# TeensySensorV6_1.net
KiCad netlist of a schematic drawn in EasyEDA Pro
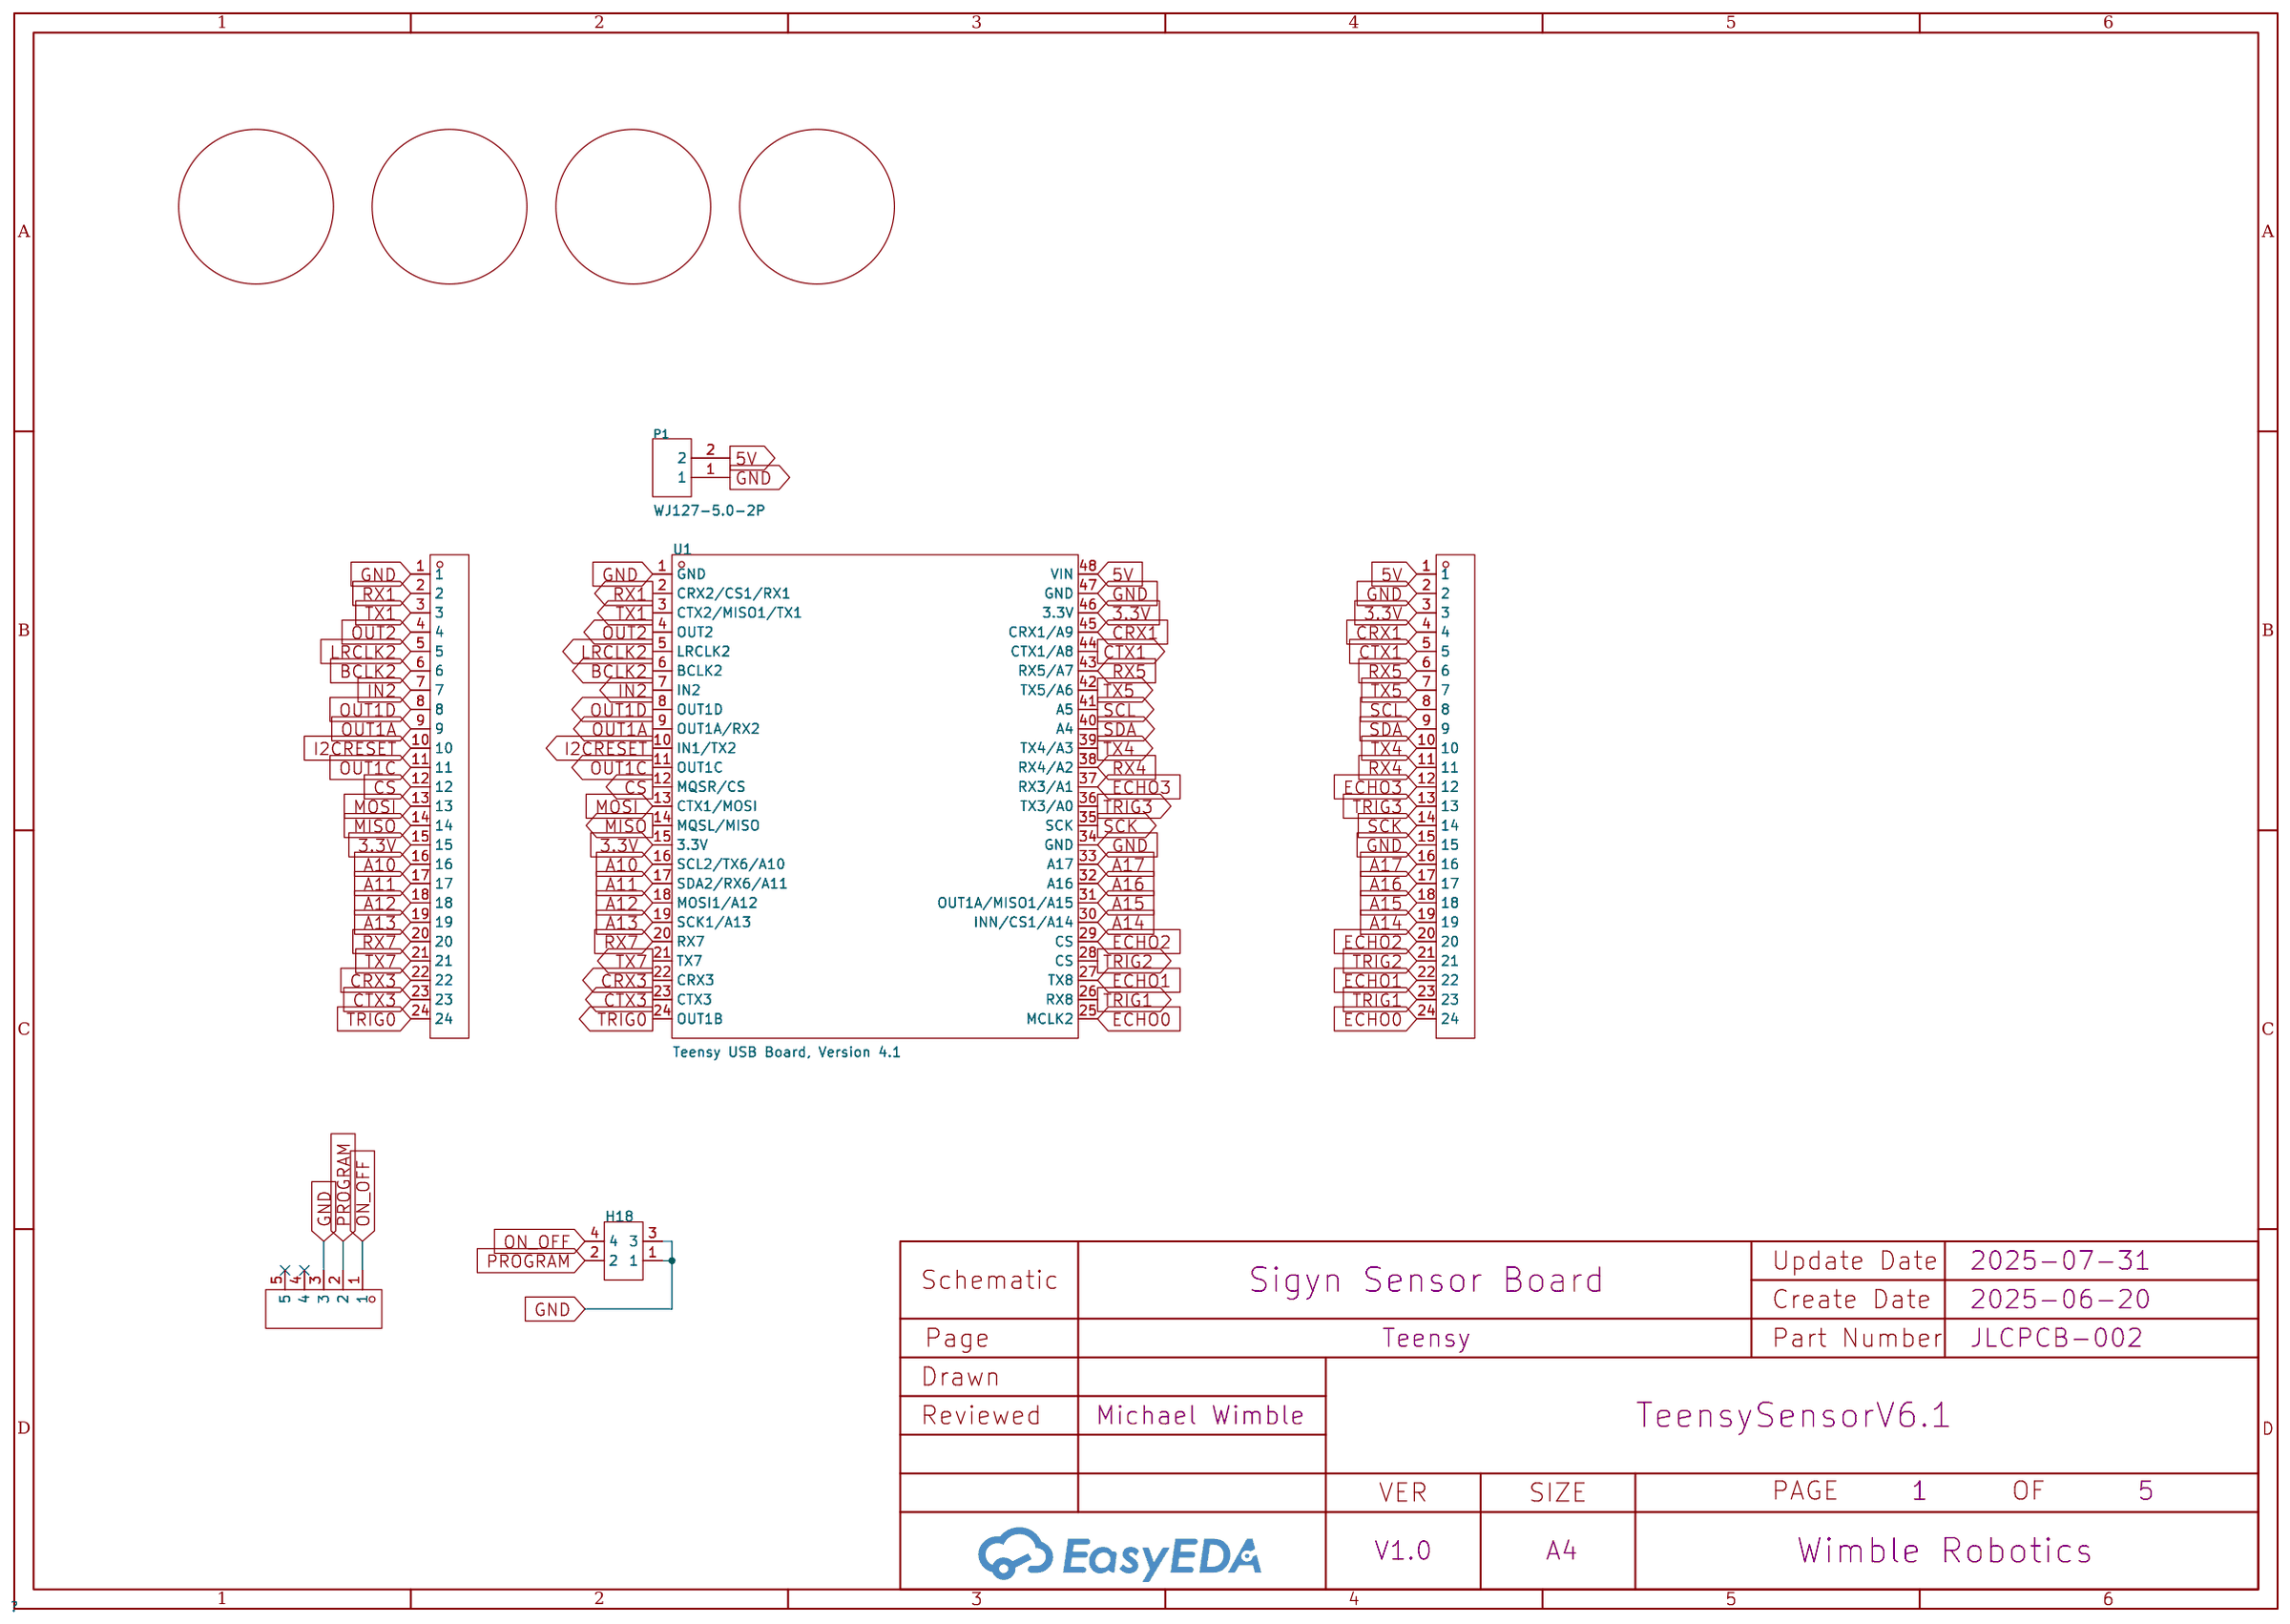
[diagram p0: Teensy]
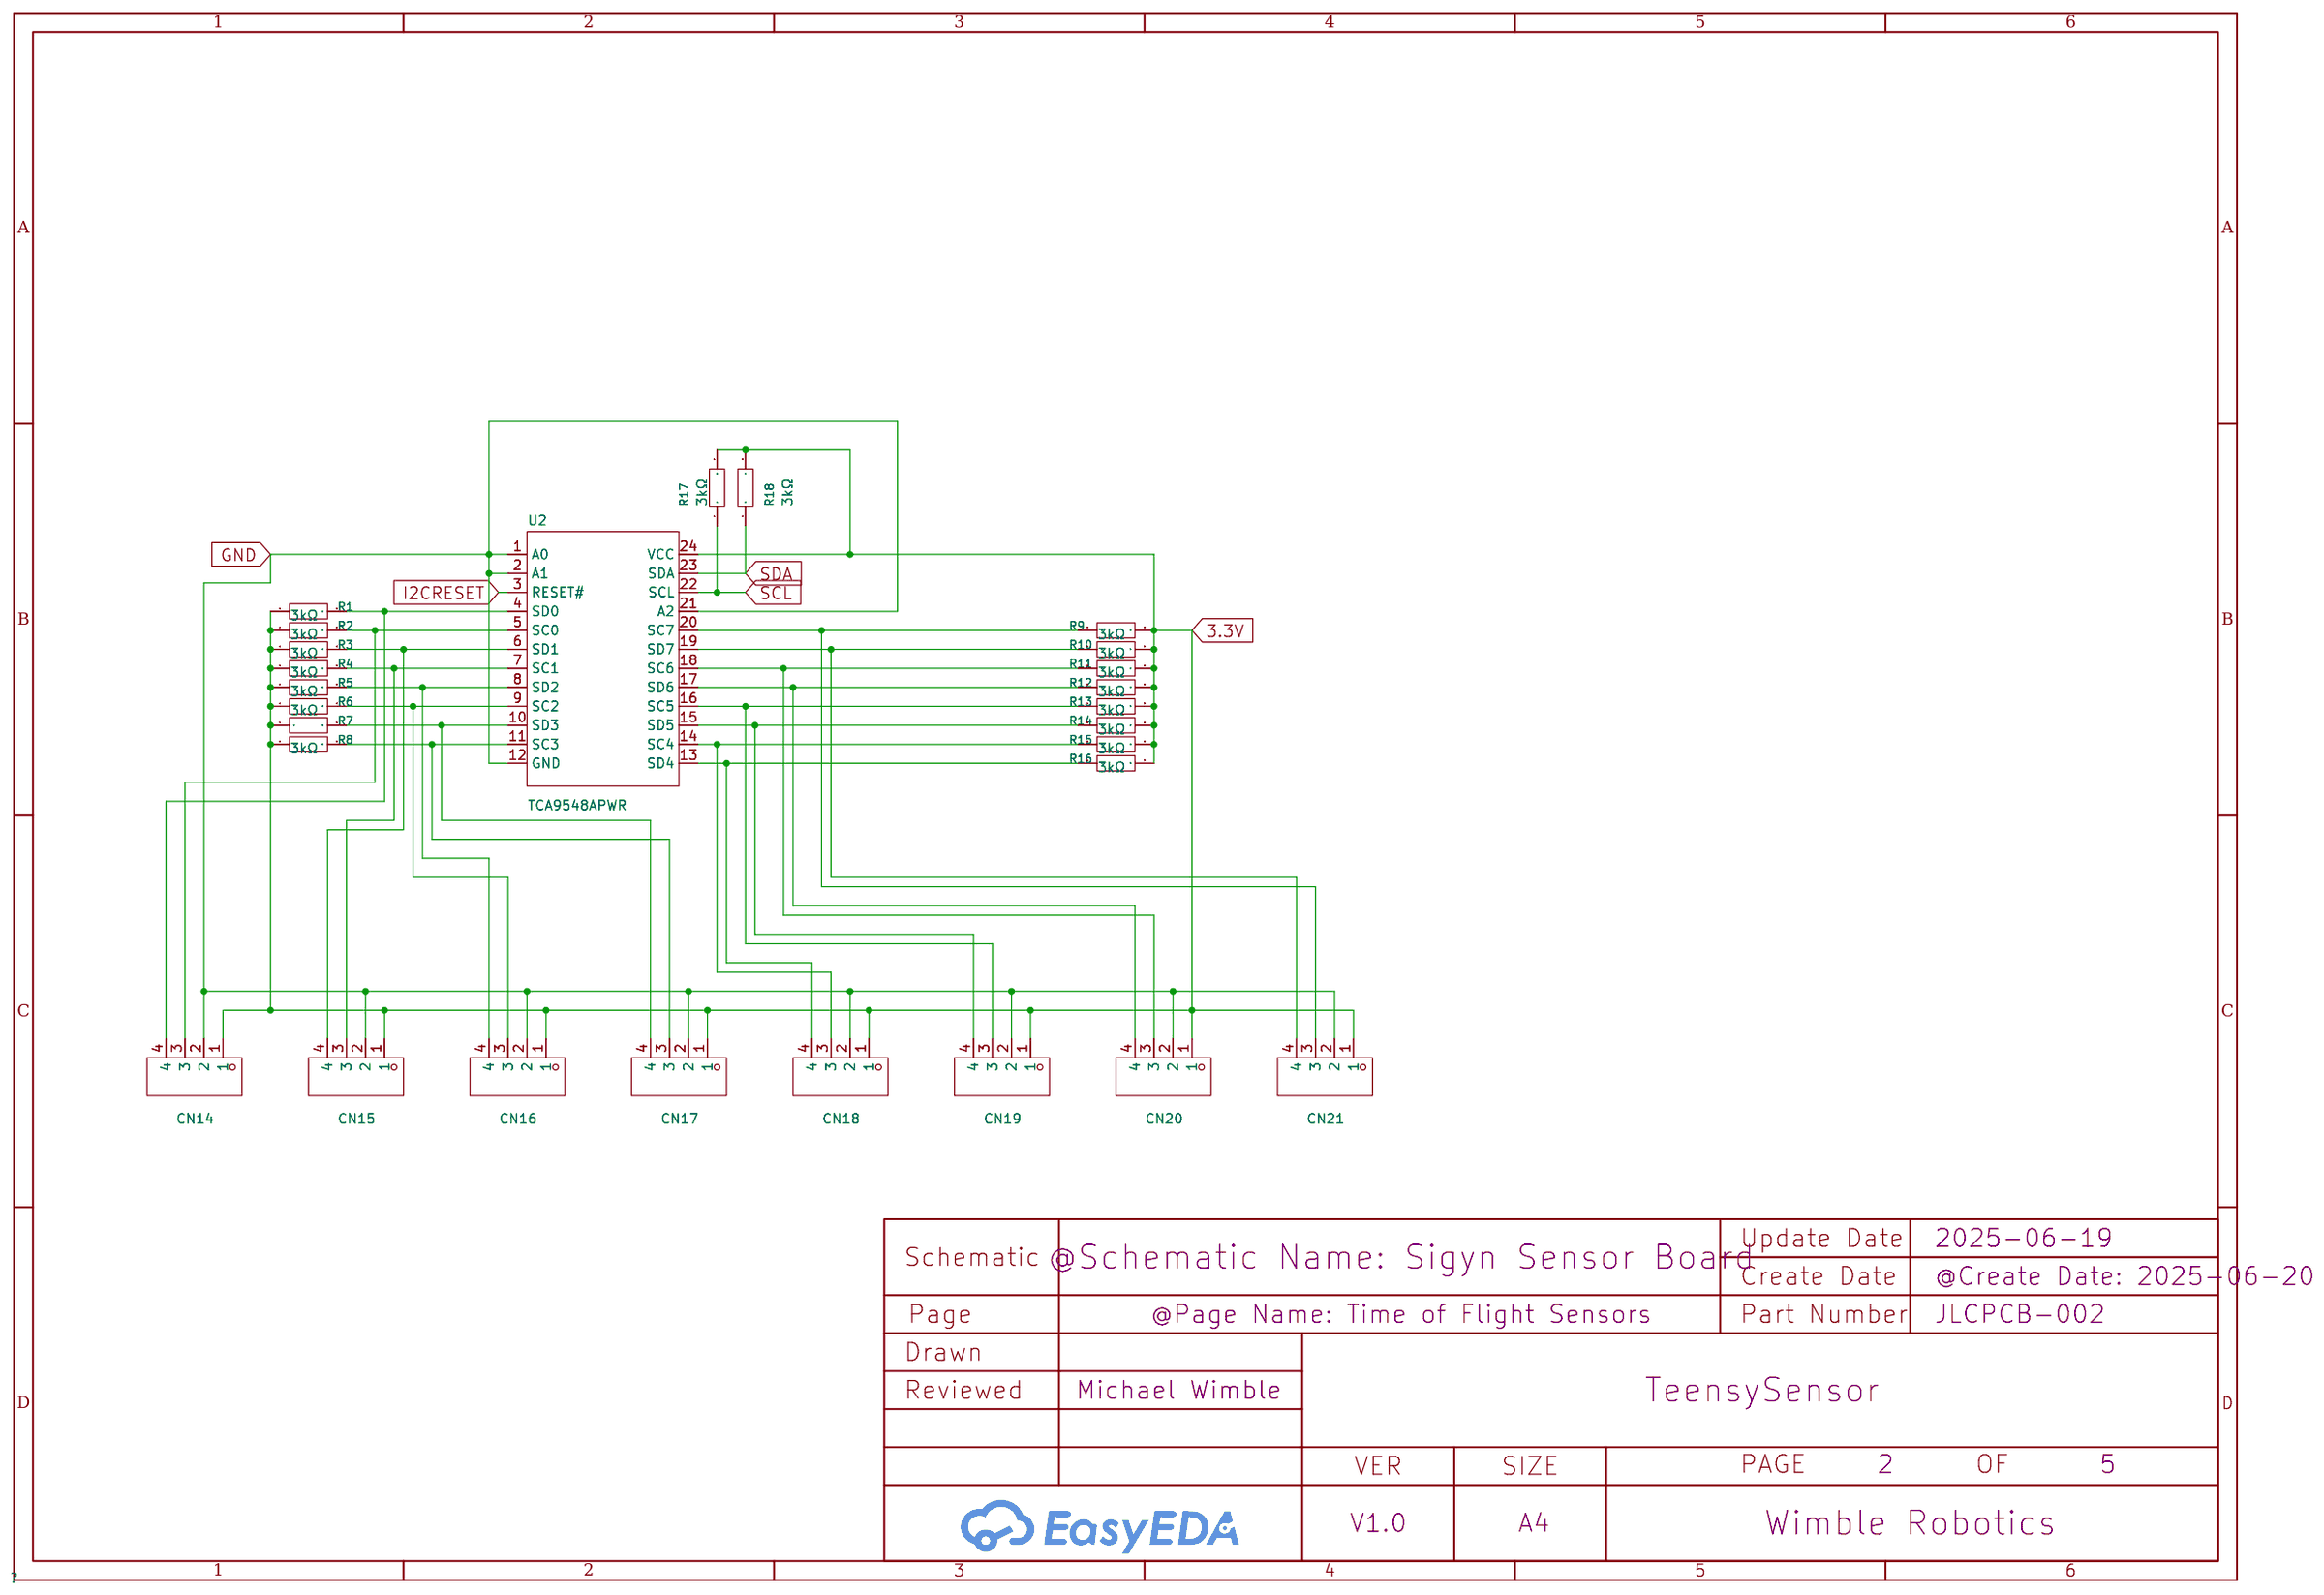
[diagram p1: Time of Flight Sensors]
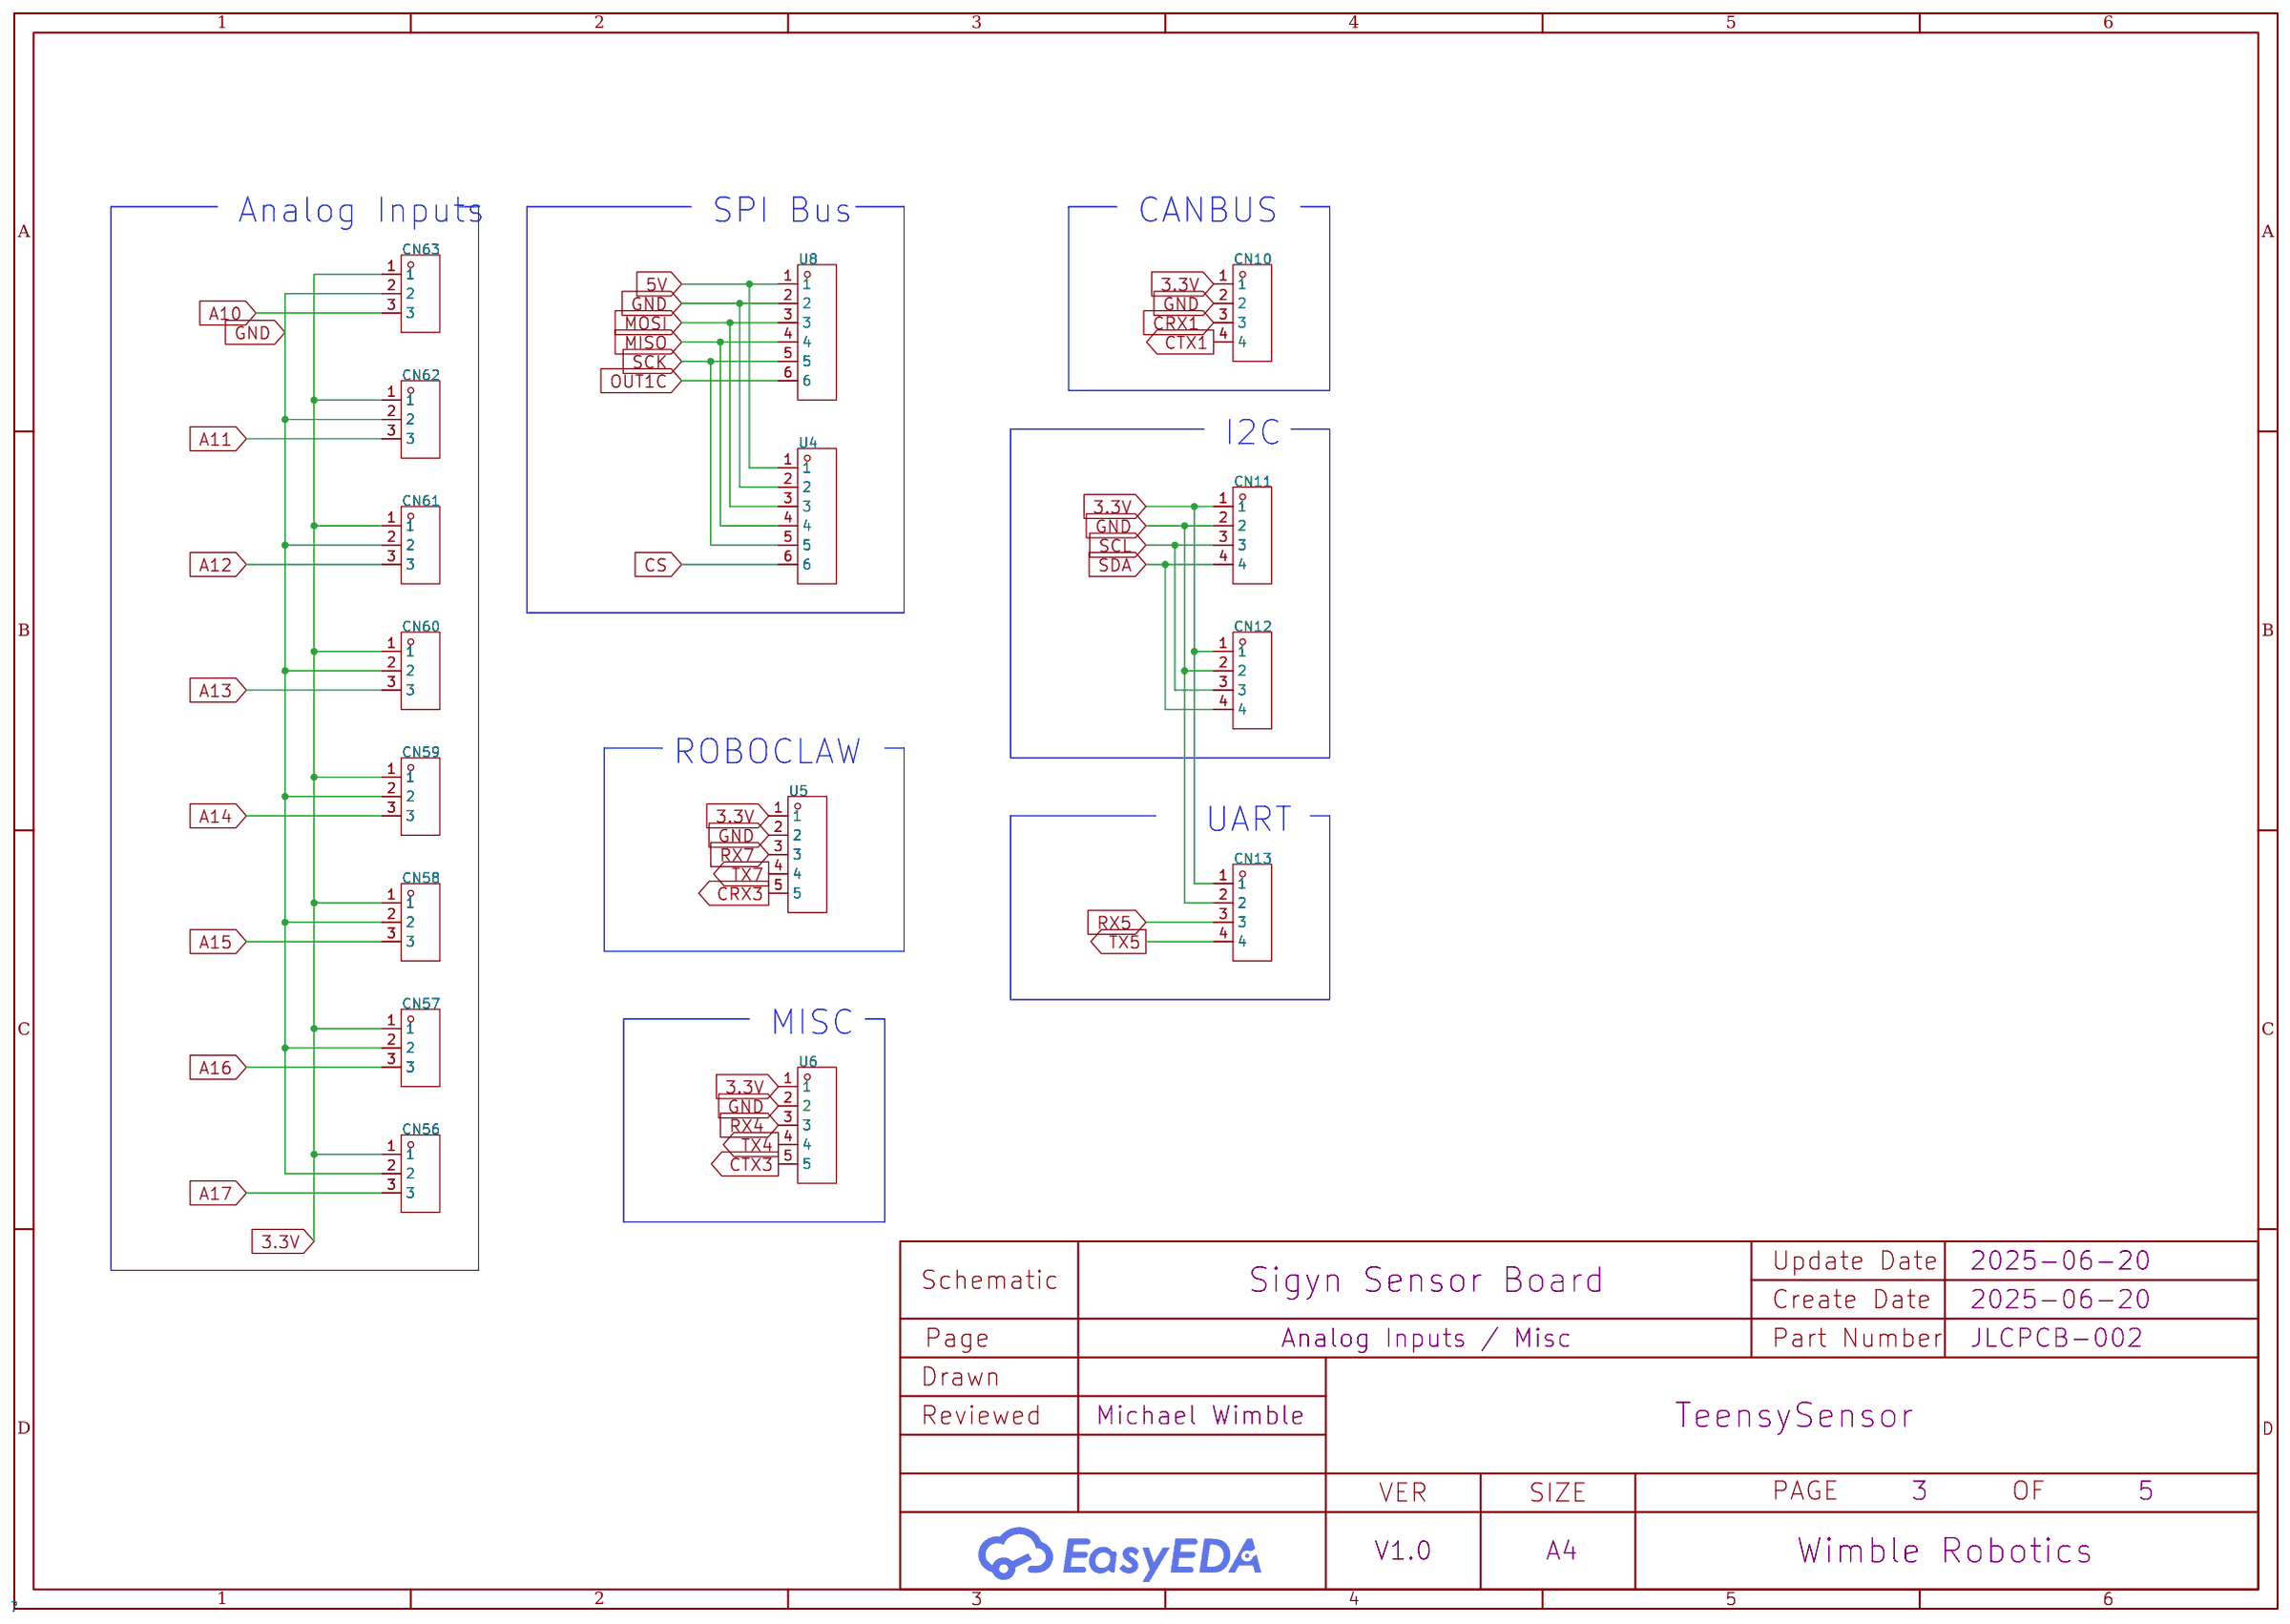
[diagram p2: Analog Inputs / Misc]
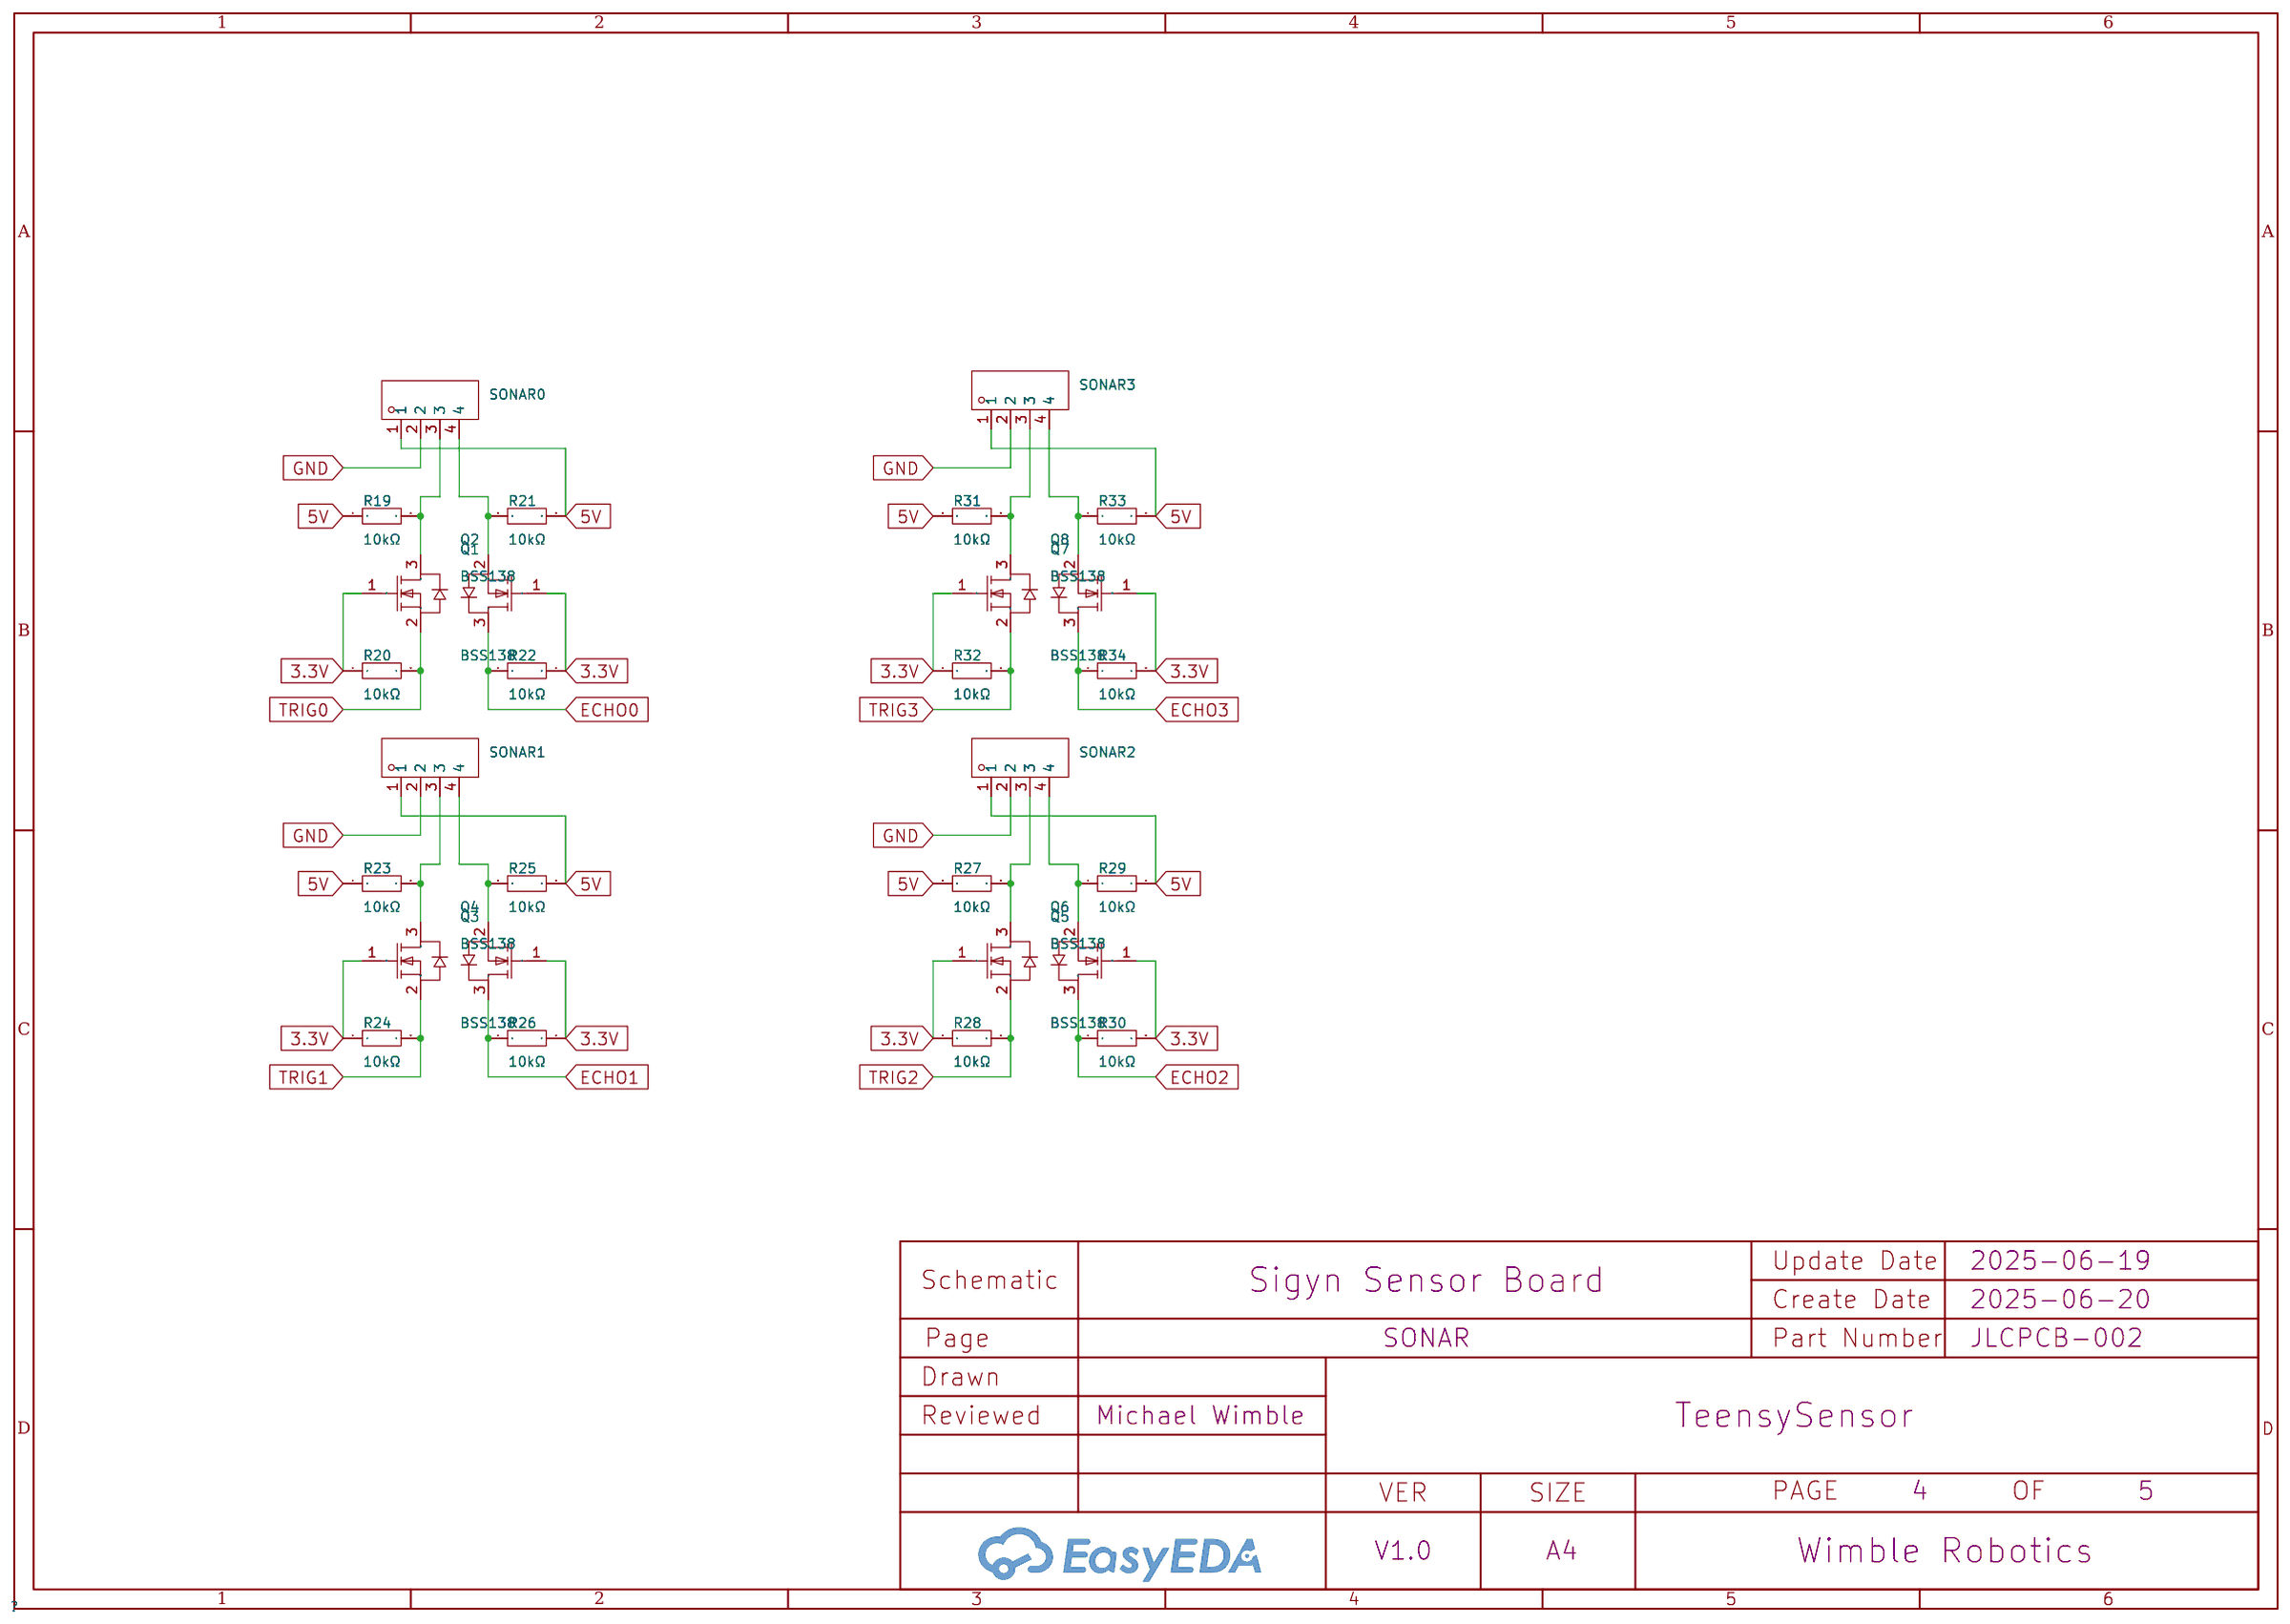
[diagram p3: SONAR]
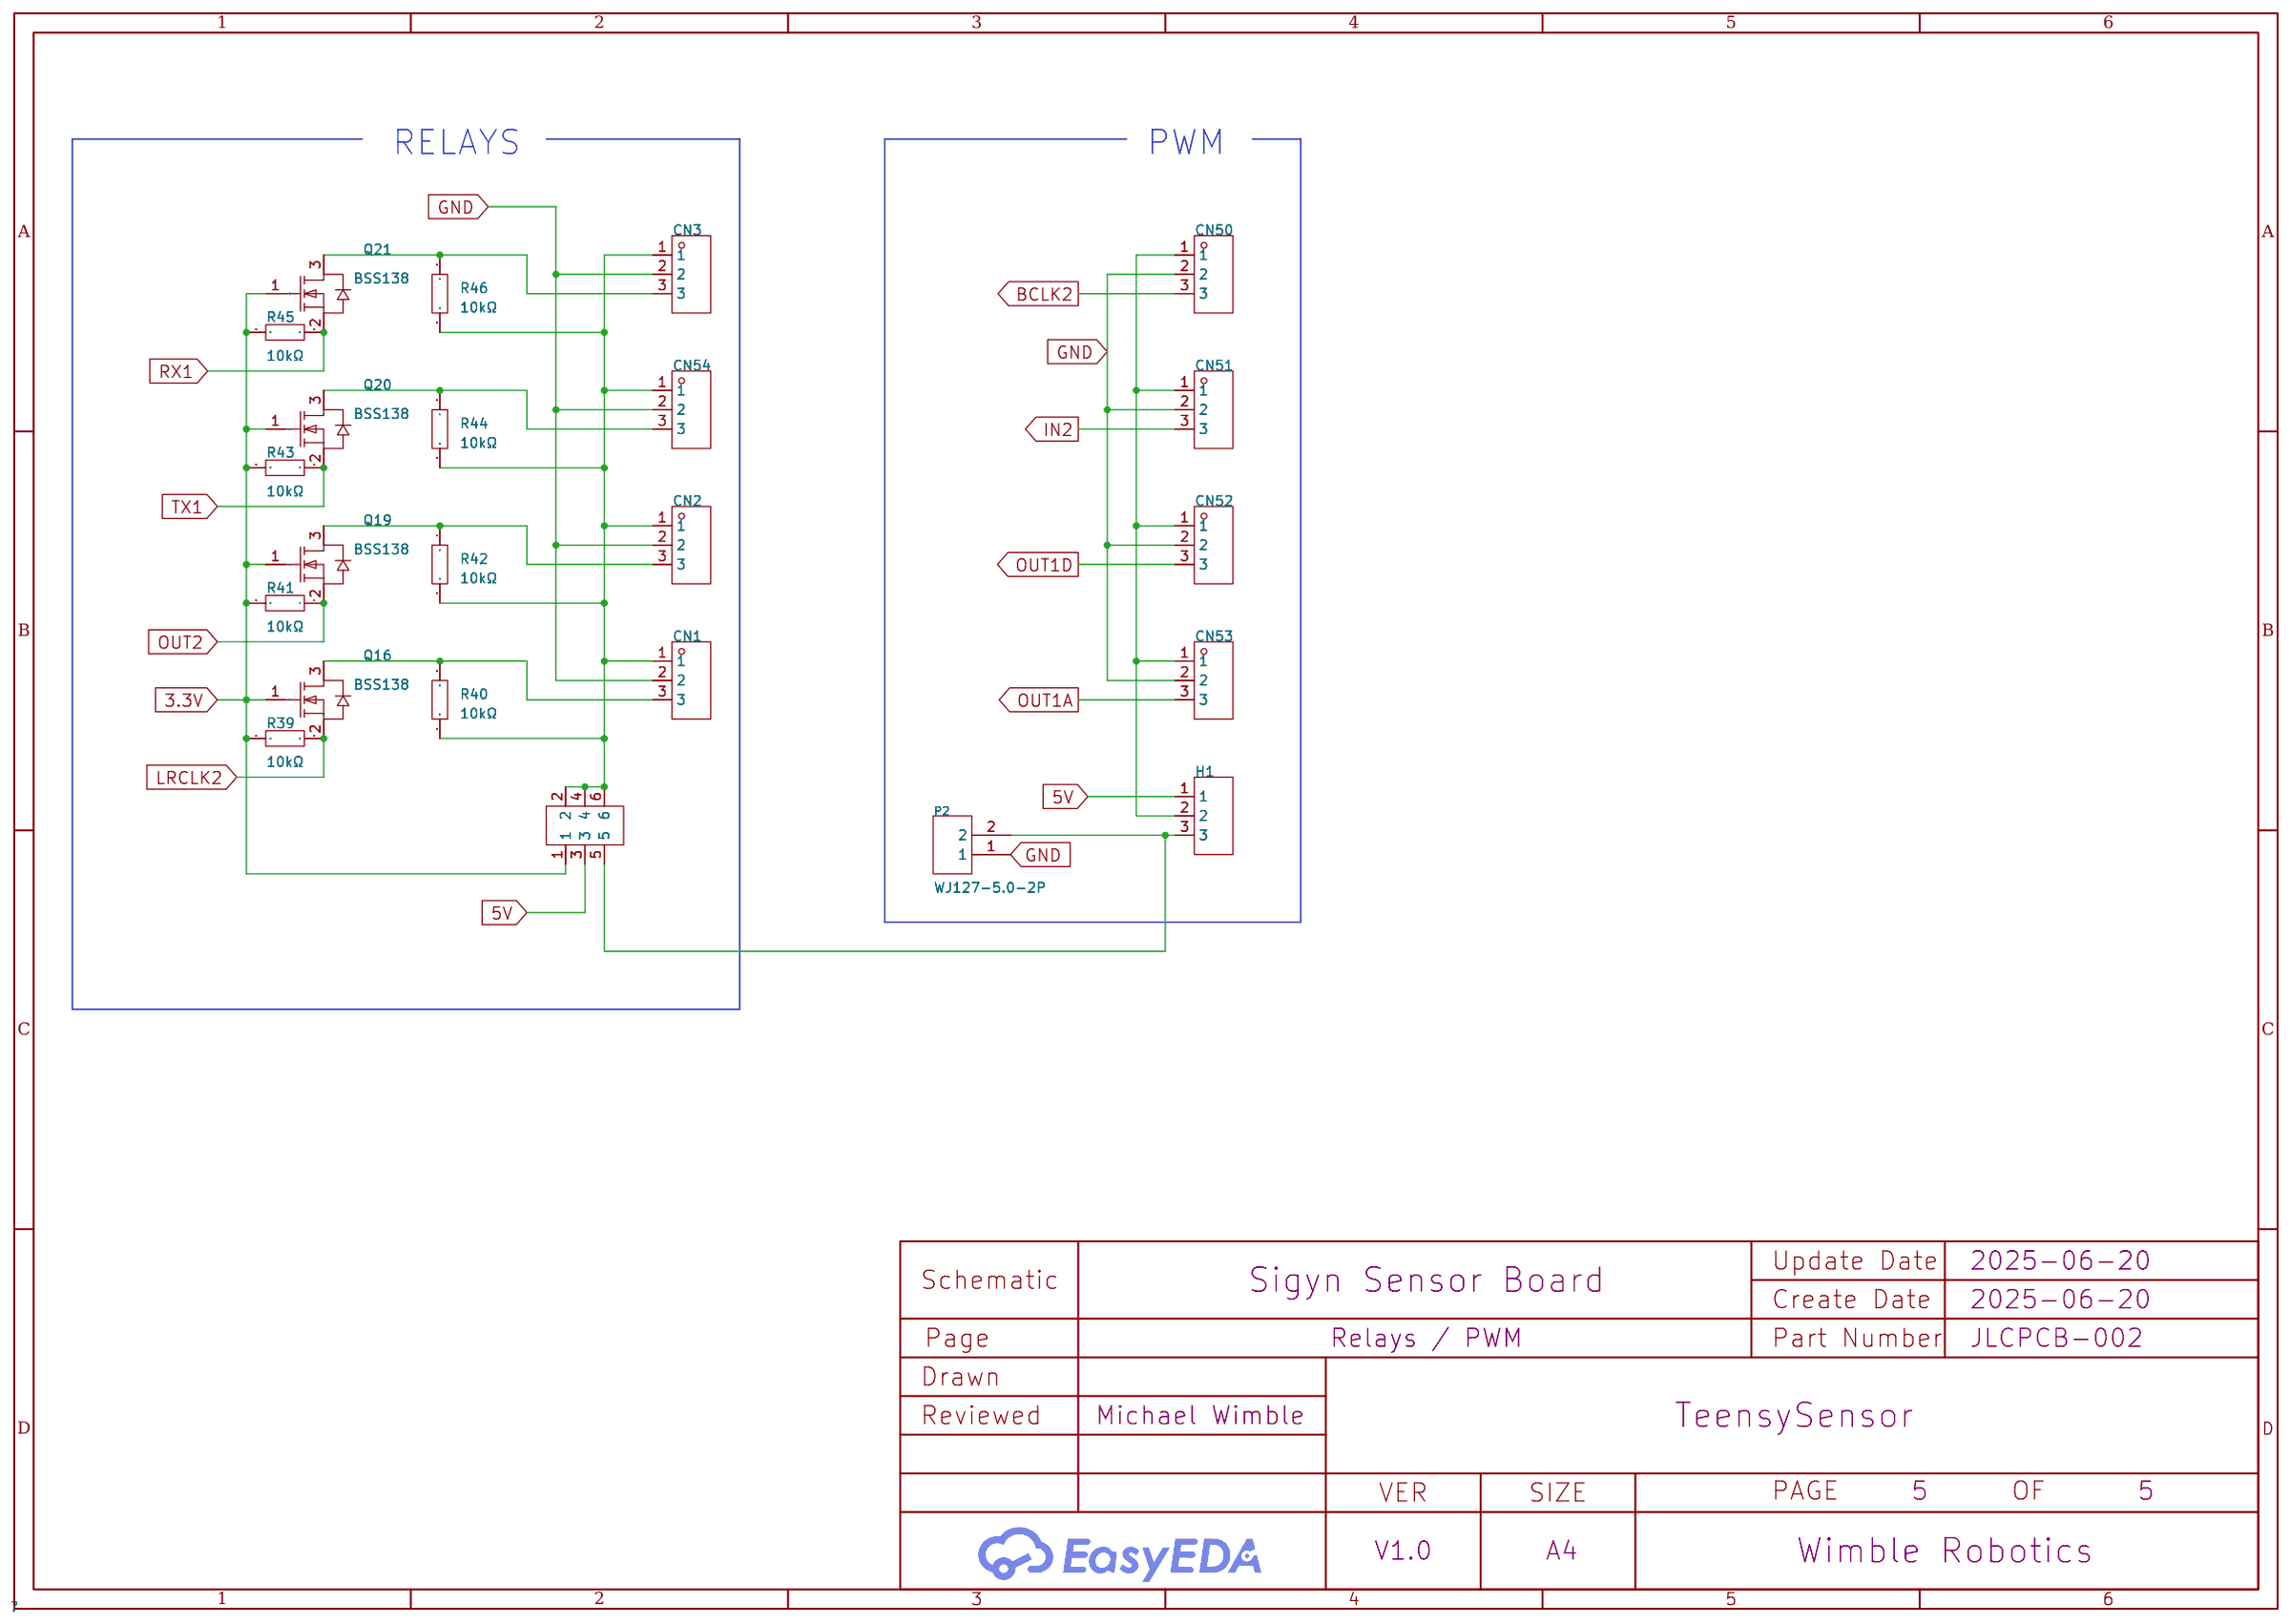
[diagram p4: Relays / PWM]

(export (version "E")
  (design (tool "Eeschema 10.0.6"))
  (components
    (comp (ref "H18")
      (value "HX PZ2.54-2x2P ZZ")
      (footprint "easyedapro:HDR-TH_HX-PZ2.54-2X2P-ZZ")
      (fields (field (name "Manufacturer") "hanxia(韩下)"))
      (libsource (lib "easyedapro") (part "HX PZ2.54-2X2P ZZ"))
    )
    (comp (ref "P1")
      (value "WJ127-5.0-2P")
      (footprint "easyedapro:CONN-TH_2P-P5.00_CPC3703CTR")
      (fields (field (name "Manufacturer") "KANGNEX(康奈克斯电气)"))
      (libsource (lib "easyedapro") (part "WJ127-5.0-2P"))
    )
    (comp (ref "U1")
      (value "Teensy USB Board, Version 4.1")
      (footprint "easyedapro:COMM-TH_L61.0-W17.8-P2.54")
      (libsource (lib "easyedapro") (part "TEENSY USB BOARD, VERSION 4.1"))
    )
    (comp (ref "U12")
      (value "~")
      (footprint "easyedapro:3.5mm_Hole")
      (description "Mounting hole")
      (libsource (lib "easyedapro") (part "3.5MMHole"))
    )
    (comp (ref "U13")
      (value "~")
      (footprint "easyedapro:3.5mm_Hole")
      (description "Mounting hole")
      (libsource (lib "easyedapro") (part "3.5MMHole"))
    )
    (comp (ref "U14")
      (value "~")
      (footprint "easyedapro:3.5mm_Hole")
      (description "Mounting hole")
      (libsource (lib "easyedapro") (part "3.5MMHole"))
    )
    (comp (ref "U15")
      (value "~")
      (footprint "easyedapro:3.5mm_Hole")
      (description "Mounting hole")
      (libsource (lib "easyedapro") (part "3.5MMHole"))
    )
    (comp (ref "U43")
      (value "HC-PM254-8.5H-1x24PZ")
      (footprint "easyedapro:HDR-TH_24P-P2.54-V-F")
      (fields (field (name "Manufacturer") "HC(虹成电子)"))
      (libsource (lib "easyedapro") (part "HC-PM254-8.5H-1X24PZ"))
    )
    (comp (ref "U44")
      (value "HC-PM254-8.5H-1x24PZ")
      (footprint "easyedapro:HDR-TH_24P-P2.54-V-F")
      (fields (field (name "Manufacturer") "HC(虹成电子)"))
      (libsource (lib "easyedapro") (part "HC-PM254-8.5H-1X24PZ"))
    )
    (comp (ref "U48")
      (value "PM2.54-1*5")
      (footprint "easyedapro:HDR-TH_5P-P2.54-V-F")
      (fields (field (name "Manufacturer") "ZHOURI(洲日)"))
      (libsource (lib "easyedapro") (part "PM2.54-1*5"))
    )
    (comp (ref "CN14")
      (value "ZX-XH2.54-4PZZ")
      (footprint "easyedapro:CONN-TH_4P-P2.50_4PIN")
      (fields (field (name "Manufacturer") "Megastar(兆星)"))
      (libsource (lib "easyedapro") (part "ZX-XH2.54-4PZZ"))
    )
    (comp (ref "CN15")
      (value "ZX-XH2.54-4PZZ")
      (footprint "easyedapro:CONN-TH_4P-P2.50_4PIN")
      (fields (field (name "Manufacturer") "Megastar(兆星)"))
      (libsource (lib "easyedapro") (part "ZX-XH2.54-4PZZ"))
    )
    (comp (ref "CN16")
      (value "ZX-XH2.54-4PZZ")
      (footprint "easyedapro:CONN-TH_4P-P2.50_4PIN")
      (fields (field (name "Manufacturer") "Megastar(兆星)"))
      (libsource (lib "easyedapro") (part "ZX-XH2.54-4PZZ"))
    )
    (comp (ref "CN17")
      (value "ZX-XH2.54-4PZZ")
      (footprint "easyedapro:CONN-TH_4P-P2.50_4PIN")
      (fields (field (name "Manufacturer") "Megastar(兆星)"))
      (libsource (lib "easyedapro") (part "ZX-XH2.54-4PZZ"))
    )
    (comp (ref "CN18")
      (value "ZX-XH2.54-4PZZ")
      (footprint "easyedapro:CONN-TH_4P-P2.50_4PIN")
      (fields (field (name "Manufacturer") "Megastar(兆星)"))
      (libsource (lib "easyedapro") (part "ZX-XH2.54-4PZZ"))
    )
    (comp (ref "CN19")
      (value "ZX-XH2.54-4PZZ")
      (footprint "easyedapro:CONN-TH_4P-P2.50_4PIN")
      (fields (field (name "Manufacturer") "Megastar(兆星)"))
      (libsource (lib "easyedapro") (part "ZX-XH2.54-4PZZ"))
    )
    (comp (ref "CN20")
      (value "ZX-XH2.54-4PZZ")
      (footprint "easyedapro:CONN-TH_4P-P2.50_4PIN")
      (fields (field (name "Manufacturer") "Megastar(兆星)"))
      (libsource (lib "easyedapro") (part "ZX-XH2.54-4PZZ"))
    )
    (comp (ref "CN21")
      (value "ZX-XH2.54-4PZZ")
      (footprint "easyedapro:CONN-TH_4P-P2.50_4PIN")
      (fields (field (name "Manufacturer") "Megastar(兆星)"))
      (libsource (lib "easyedapro") (part "ZX-XH2.54-4PZZ"))
    )
    (comp (ref "R1")
      (value "3kΩ")
      (footprint "easyedapro:R0603")
      (fields
        (field (name "Manufacturer Part") "0603WAF3001T5E")
        (field (name "Manufacturer") "UNI-ROYAL(厚声)")
      )
      (libsource (lib "easyedapro") (part "0603WAF3001T5E"))
    )
    (comp (ref "R2")
      (value "3kΩ")
      (footprint "easyedapro:R0603")
      (fields
        (field (name "Manufacturer Part") "0603WAF3001T5E")
        (field (name "Manufacturer") "UNI-ROYAL(厚声)")
      )
      (libsource (lib "easyedapro") (part "0603WAF3001T5E"))
    )
    (comp (ref "R3")
      (value "3kΩ")
      (footprint "easyedapro:R0603")
      (fields
        (field (name "Manufacturer Part") "0603WAF3001T5E")
        (field (name "Manufacturer") "UNI-ROYAL(厚声)")
      )
      (libsource (lib "easyedapro") (part "0603WAF3001T5E"))
    )
    (comp (ref "R4")
      (value "3kΩ")
      (footprint "easyedapro:R0603")
      (fields
        (field (name "Manufacturer Part") "0603WAF3001T5E")
        (field (name "Manufacturer") "UNI-ROYAL(厚声)")
      )
      (libsource (lib "easyedapro") (part "0603WAF3001T5E"))
    )
    (comp (ref "R5")
      (value "3kΩ")
      (footprint "easyedapro:R0603")
      (fields
        (field (name "Manufacturer Part") "0603WAF3001T5E")
        (field (name "Manufacturer") "UNI-ROYAL(厚声)")
      )
      (libsource (lib "easyedapro") (part "0603WAF3001T5E"))
    )
    (comp (ref "R6")
      (value "3kΩ")
      (footprint "easyedapro:R0603")
      (fields
        (field (name "Manufacturer Part") "0603WAF3001T5E")
        (field (name "Manufacturer") "UNI-ROYAL(厚声)")
      )
      (libsource (lib "easyedapro") (part "0603WAF3001T5E"))
    )
    (comp (ref "R7")
      (value "3kΩ")
      (footprint "easyedapro:R0603")
      (fields
        (field (name "Manufacturer Part") "0603WAF3001T5E")
        (field (name "Manufacturer") "UNI-ROYAL(厚声)")
      )
      (libsource (lib "easyedapro") (part "0603WAF3001T5E"))
    )
    (comp (ref "R8")
      (value "3kΩ")
      (footprint "easyedapro:R0603")
      (fields
        (field (name "Manufacturer Part") "0603WAF3001T5E")
        (field (name "Manufacturer") "UNI-ROYAL(厚声)")
      )
      (libsource (lib "easyedapro") (part "0603WAF3001T5E"))
    )
    (comp (ref "R9")
      (value "3kΩ")
      (footprint "easyedapro:R0603")
      (fields
        (field (name "Manufacturer Part") "0603WAF3001T5E")
        (field (name "Manufacturer") "UNI-ROYAL(厚声)")
      )
      (libsource (lib "easyedapro") (part "0603WAF3001T5E"))
    )
    (comp (ref "R10")
      (value "3kΩ")
      (footprint "easyedapro:R0603")
      (fields
        (field (name "Manufacturer Part") "0603WAF3001T5E")
        (field (name "Manufacturer") "UNI-ROYAL(厚声)")
      )
      (libsource (lib "easyedapro") (part "0603WAF3001T5E"))
    )
    (comp (ref "R11")
      (value "3kΩ")
      (footprint "easyedapro:R0603")
      (fields
        (field (name "Manufacturer Part") "0603WAF3001T5E")
        (field (name "Manufacturer") "UNI-ROYAL(厚声)")
      )
      (libsource (lib "easyedapro") (part "0603WAF3001T5E"))
    )
    (comp (ref "R12")
      (value "3kΩ")
      (footprint "easyedapro:R0603")
      (fields
        (field (name "Manufacturer Part") "0603WAF3001T5E")
        (field (name "Manufacturer") "UNI-ROYAL(厚声)")
      )
      (libsource (lib "easyedapro") (part "0603WAF3001T5E"))
    )
    (comp (ref "R13")
      (value "3kΩ")
      (footprint "easyedapro:R0603")
      (fields
        (field (name "Manufacturer Part") "0603WAF3001T5E")
        (field (name "Manufacturer") "UNI-ROYAL(厚声)")
      )
      (libsource (lib "easyedapro") (part "0603WAF3001T5E"))
    )
    (comp (ref "R14")
      (value "3kΩ")
      (footprint "easyedapro:R0603")
      (fields
        (field (name "Manufacturer Part") "0603WAF3001T5E")
        (field (name "Manufacturer") "UNI-ROYAL(厚声)")
      )
      (libsource (lib "easyedapro") (part "0603WAF3001T5E"))
    )
    (comp (ref "R15")
      (value "3kΩ")
      (footprint "easyedapro:R0603")
      (fields
        (field (name "Manufacturer Part") "0603WAF3001T5E")
        (field (name "Manufacturer") "UNI-ROYAL(厚声)")
      )
      (libsource (lib "easyedapro") (part "0603WAF3001T5E"))
    )
    (comp (ref "R16")
      (value "3kΩ")
      (footprint "easyedapro:R0603")
      (fields
        (field (name "Manufacturer Part") "0603WAF3001T5E")
        (field (name "Manufacturer") "UNI-ROYAL(厚声)")
      )
      (libsource (lib "easyedapro") (part "0603WAF3001T5E"))
    )
    (comp (ref "R17")
      (value "3kΩ")
      (footprint "easyedapro:R0603")
      (fields
        (field (name "Manufacturer Part") "0603WAF3001T5E")
        (field (name "Manufacturer") "UNI-ROYAL(厚声)")
      )
      (libsource (lib "easyedapro") (part "0603WAF3001T5E"))
    )
    (comp (ref "R18")
      (value "3kΩ")
      (footprint "easyedapro:R0603")
      (fields
        (field (name "Manufacturer Part") "0603WAF3001T5E")
        (field (name "Manufacturer") "UNI-ROYAL(厚声)")
      )
      (libsource (lib "easyedapro") (part "0603WAF3001T5E"))
    )
    (comp (ref "U2")
      (value "TCA9548APWR")
      (footprint "easyedapro:TSSOP-24_L7.8-W4.4-P0.65-LS6.4-BL")
      (fields (field (name "Manufacturer") "TI(德州仪器)"))
      (libsource (lib "easyedapro") (part "TCA9548APWR"))
    )
    (comp (ref "CN10")
      (value "ZX-XH2.54-4PZZ")
      (footprint "easyedapro:CONN-TH_4P-P2.50_4PIN")
      (fields (field (name "Manufacturer") "Megastar(兆星)"))
      (libsource (lib "easyedapro") (part "ZX-XH2.54-4PZZ"))
    )
    (comp (ref "CN11")
      (value "ZX-XH2.54-4PZZ")
      (footprint "easyedapro:CONN-TH_4P-P2.50_4PIN")
      (fields (field (name "Manufacturer") "Megastar(兆星)"))
      (libsource (lib "easyedapro") (part "ZX-XH2.54-4PZZ"))
    )
    (comp (ref "CN12")
      (value "ZX-XH2.54-4PZZ")
      (footprint "easyedapro:CONN-TH_4P-P2.50_4PIN")
      (fields (field (name "Manufacturer") "Megastar(兆星)"))
      (libsource (lib "easyedapro") (part "ZX-XH2.54-4PZZ"))
    )
    (comp (ref "CN13")
      (value "ZX-XH2.54-4PZZ")
      (footprint "easyedapro:CONN-TH_4P-P2.50_4PIN")
      (fields (field (name "Manufacturer") "Megastar(兆星)"))
      (libsource (lib "easyedapro") (part "ZX-XH2.54-4PZZ"))
    )
    (comp (ref "CN56")
      (value "ZX-XH2.54-3PZZ")
      (footprint "easyedapro:CONN-TH_3P-P2.54_2501S-3P")
      (fields (field (name "Manufacturer") "Megastar(兆星)"))
      (libsource (lib "easyedapro") (part "ZX-XH2.54-3PZZ"))
    )
    (comp (ref "CN57")
      (value "ZX-XH2.54-3PZZ")
      (footprint "easyedapro:CONN-TH_3P-P2.54_2501S-3P")
      (fields (field (name "Manufacturer") "Megastar(兆星)"))
      (libsource (lib "easyedapro") (part "ZX-XH2.54-3PZZ"))
    )
    (comp (ref "CN58")
      (value "ZX-XH2.54-3PZZ")
      (footprint "easyedapro:CONN-TH_3P-P2.54_2501S-3P")
      (fields (field (name "Manufacturer") "Megastar(兆星)"))
      (libsource (lib "easyedapro") (part "ZX-XH2.54-3PZZ"))
    )
    (comp (ref "CN59")
      (value "ZX-XH2.54-3PZZ")
      (footprint "easyedapro:CONN-TH_3P-P2.54_2501S-3P")
      (fields (field (name "Manufacturer") "Megastar(兆星)"))
      (libsource (lib "easyedapro") (part "ZX-XH2.54-3PZZ"))
    )
    (comp (ref "CN60")
      (value "ZX-XH2.54-3PZZ")
      (footprint "easyedapro:CONN-TH_3P-P2.54_2501S-3P")
      (fields (field (name "Manufacturer") "Megastar(兆星)"))
      (libsource (lib "easyedapro") (part "ZX-XH2.54-3PZZ"))
    )
    (comp (ref "CN61")
      (value "ZX-XH2.54-3PZZ")
      (footprint "easyedapro:CONN-TH_3P-P2.54_2501S-3P")
      (fields (field (name "Manufacturer") "Megastar(兆星)"))
      (libsource (lib "easyedapro") (part "ZX-XH2.54-3PZZ"))
    )
    (comp (ref "CN62")
      (value "ZX-XH2.54-3PZZ")
      (footprint "easyedapro:CONN-TH_3P-P2.54_2501S-3P")
      (fields (field (name "Manufacturer") "Megastar(兆星)"))
      (libsource (lib "easyedapro") (part "ZX-XH2.54-3PZZ"))
    )
    (comp (ref "CN63")
      (value "ZX-XH2.54-3PZZ")
      (footprint "easyedapro:CONN-TH_3P-P2.54_2501S-3P")
      (fields (field (name "Manufacturer") "Megastar(兆星)"))
      (libsource (lib "easyedapro") (part "ZX-XH2.54-3PZZ"))
    )
    (comp (ref "U4")
      (value "ZX-XH2.54-6PZZ")
      (footprint "easyedapro:CONN-TH_6P-P2.50_ZX-XH2.54-6PZZ")
      (fields (field (name "Manufacturer") "Megastar(兆星)"))
      (libsource (lib "easyedapro") (part "ZX-XH2.54-6PZZ"))
    )
    (comp (ref "U5")
      (value "ZX-XH2.54-5PZZ")
      (footprint "easyedapro:CONN-TH_5P-P2.50_ZX-XH2.54-5PZZ")
      (fields (field (name "Manufacturer") "Megastar(兆星)"))
      (libsource (lib "easyedapro") (part "ZX-XH2.54-5PZZ"))
    )
    (comp (ref "U6")
      (value "ZX-XH2.54-5PZZ")
      (footprint "easyedapro:CONN-TH_5P-P2.50_ZX-XH2.54-5PZZ")
      (fields (field (name "Manufacturer") "Megastar(兆星)"))
      (libsource (lib "easyedapro") (part "ZX-XH2.54-5PZZ"))
    )
    (comp (ref "U8")
      (value "ZX-XH2.54-6PZZ")
      (footprint "easyedapro:CONN-TH_6P-P2.50_ZX-XH2.54-6PZZ")
      (fields (field (name "Manufacturer") "Megastar(兆星)"))
      (libsource (lib "easyedapro") (part "ZX-XH2.54-6PZZ"))
    )
    (comp (ref "Q1")
      (value "BSS138")
      (footprint "easyedapro:SOT-23-3_L2.9-W1.6-P1.90-LS2.8-BR")
      (fields (field (name "Manufacturer") "TECH PUBLIC(台舟)"))
      (libsource (lib "easyedapro") (part "BSS138_C18212695"))
    )
    (comp (ref "Q2")
      (value "BSS138")
      (footprint "easyedapro:SOT-23-3_L2.9-W1.6-P1.90-LS2.8-BR")
      (fields (field (name "Manufacturer") "TECH PUBLIC(台舟)"))
      (libsource (lib "easyedapro") (part "BSS138_C18212695"))
    )
    (comp (ref "Q3")
      (value "BSS138")
      (footprint "easyedapro:SOT-23-3_L2.9-W1.6-P1.90-LS2.8-BR")
      (fields (field (name "Manufacturer") "TECH PUBLIC(台舟)"))
      (libsource (lib "easyedapro") (part "BSS138_C18212695"))
    )
    (comp (ref "Q4")
      (value "BSS138")
      (footprint "easyedapro:SOT-23-3_L2.9-W1.6-P1.90-LS2.8-BR")
      (fields (field (name "Manufacturer") "TECH PUBLIC(台舟)"))
      (libsource (lib "easyedapro") (part "BSS138_C18212695"))
    )
    (comp (ref "Q5")
      (value "BSS138")
      (footprint "easyedapro:SOT-23-3_L2.9-W1.6-P1.90-LS2.8-BR")
      (fields (field (name "Manufacturer") "TECH PUBLIC(台舟)"))
      (libsource (lib "easyedapro") (part "BSS138_C18212695"))
    )
    (comp (ref "Q6")
      (value "BSS138")
      (footprint "easyedapro:SOT-23-3_L2.9-W1.6-P1.90-LS2.8-BR")
      (fields (field (name "Manufacturer") "TECH PUBLIC(台舟)"))
      (libsource (lib "easyedapro") (part "BSS138_C18212695"))
    )
    (comp (ref "Q7")
      (value "BSS138")
      (footprint "easyedapro:SOT-23-3_L2.9-W1.6-P1.90-LS2.8-BR")
      (fields (field (name "Manufacturer") "TECH PUBLIC(台舟)"))
      (libsource (lib "easyedapro") (part "BSS138_C18212695"))
    )
    (comp (ref "Q8")
      (value "BSS138")
      (footprint "easyedapro:SOT-23-3_L2.9-W1.6-P1.90-LS2.8-BR")
      (fields (field (name "Manufacturer") "TECH PUBLIC(台舟)"))
      (libsource (lib "easyedapro") (part "BSS138_C18212695"))
    )
    (comp (ref "R19")
      (value "10kΩ")
      (footprint "easyedapro:R0603")
      (fields (field (name "Manufacturer Part") "RC0603FR-0710KL") (field (name "Manufacturer") "YAGEO(国巨)"))
      (libsource (lib "easyedapro") (part "RC0603FR-0710KL"))
    )
    (comp (ref "R20")
      (value "10kΩ")
      (footprint "easyedapro:R0603")
      (fields (field (name "Manufacturer Part") "RC0603FR-0710KL") (field (name "Manufacturer") "YAGEO(国巨)"))
      (libsource (lib "easyedapro") (part "RC0603FR-0710KL"))
    )
    (comp (ref "R21")
      (value "10kΩ")
      (footprint "easyedapro:R0603")
      (fields (field (name "Manufacturer Part") "RC0603FR-0710KL") (field (name "Manufacturer") "YAGEO(国巨)"))
      (libsource (lib "easyedapro") (part "RC0603FR-0710KL"))
    )
    (comp (ref "R22")
      (value "10kΩ")
      (footprint "easyedapro:R0603")
      (fields (field (name "Manufacturer Part") "RC0603FR-0710KL") (field (name "Manufacturer") "YAGEO(国巨)"))
      (libsource (lib "easyedapro") (part "RC0603FR-0710KL"))
    )
    (comp (ref "R23")
      (value "10kΩ")
      (footprint "easyedapro:R0603")
      (fields (field (name "Manufacturer Part") "RC0603FR-0710KL") (field (name "Manufacturer") "YAGEO(国巨)"))
      (libsource (lib "easyedapro") (part "RC0603FR-0710KL"))
    )
    (comp (ref "R24")
      (value "10kΩ")
      (footprint "easyedapro:R0603")
      (fields (field (name "Manufacturer Part") "RC0603FR-0710KL") (field (name "Manufacturer") "YAGEO(国巨)"))
      (libsource (lib "easyedapro") (part "RC0603FR-0710KL"))
    )
    (comp (ref "R25")
      (value "10kΩ")
      (footprint "easyedapro:R0603")
      (fields (field (name "Manufacturer Part") "RC0603FR-0710KL") (field (name "Manufacturer") "YAGEO(国巨)"))
      (libsource (lib "easyedapro") (part "RC0603FR-0710KL"))
    )
    (comp (ref "R26")
      (value "10kΩ")
      (footprint "easyedapro:R0603")
      (fields (field (name "Manufacturer Part") "RC0603FR-0710KL") (field (name "Manufacturer") "YAGEO(国巨)"))
      (libsource (lib "easyedapro") (part "RC0603FR-0710KL"))
    )
    (comp (ref "R27")
      (value "10kΩ")
      (footprint "easyedapro:R0603")
      (fields (field (name "Manufacturer Part") "RC0603FR-0710KL") (field (name "Manufacturer") "YAGEO(国巨)"))
      (libsource (lib "easyedapro") (part "RC0603FR-0710KL"))
    )
    (comp (ref "R28")
      (value "10kΩ")
      (footprint "easyedapro:R0603")
      (fields (field (name "Manufacturer Part") "RC0603FR-0710KL") (field (name "Manufacturer") "YAGEO(国巨)"))
      (libsource (lib "easyedapro") (part "RC0603FR-0710KL"))
    )
    (comp (ref "R29")
      (value "10kΩ")
      (footprint "easyedapro:R0603")
      (fields (field (name "Manufacturer Part") "RC0603FR-0710KL") (field (name "Manufacturer") "YAGEO(国巨)"))
      (libsource (lib "easyedapro") (part "RC0603FR-0710KL"))
    )
    (comp (ref "R30")
      (value "10kΩ")
      (footprint "easyedapro:R0603")
      (fields (field (name "Manufacturer Part") "RC0603FR-0710KL") (field (name "Manufacturer") "YAGEO(国巨)"))
      (libsource (lib "easyedapro") (part "RC0603FR-0710KL"))
    )
    (comp (ref "R31")
      (value "10kΩ")
      (footprint "easyedapro:R0603")
      (fields (field (name "Manufacturer Part") "RC0603FR-0710KL") (field (name "Manufacturer") "YAGEO(国巨)"))
      (libsource (lib "easyedapro") (part "RC0603FR-0710KL"))
    )
    (comp (ref "R32")
      (value "10kΩ")
      (footprint "easyedapro:R0603")
      (fields (field (name "Manufacturer Part") "RC0603FR-0710KL") (field (name "Manufacturer") "YAGEO(国巨)"))
      (libsource (lib "easyedapro") (part "RC0603FR-0710KL"))
    )
    (comp (ref "R33")
      (value "10kΩ")
      (footprint "easyedapro:R0603")
      (fields (field (name "Manufacturer Part") "RC0603FR-0710KL") (field (name "Manufacturer") "YAGEO(国巨)"))
      (libsource (lib "easyedapro") (part "RC0603FR-0710KL"))
    )
    (comp (ref "R34")
      (value "10kΩ")
      (footprint "easyedapro:R0603")
      (fields (field (name "Manufacturer Part") "RC0603FR-0710KL") (field (name "Manufacturer") "YAGEO(国巨)"))
      (libsource (lib "easyedapro") (part "RC0603FR-0710KL"))
    )
    (comp (ref "SONAR0")
      (value "ZX-XH2.54-4PZZ")
      (footprint "easyedapro:CONN-TH_4P-P2.50_4PIN")
      (fields (field (name "Manufacturer") "Megastar(兆星)"))
      (libsource (lib "easyedapro") (part "ZX-XH2.54-4PZZ"))
    )
    (comp (ref "SONAR1")
      (value "ZX-XH2.54-4PZZ")
      (footprint "easyedapro:CONN-TH_4P-P2.50_4PIN")
      (fields (field (name "Manufacturer") "Megastar(兆星)"))
      (libsource (lib "easyedapro") (part "ZX-XH2.54-4PZZ"))
    )
    (comp (ref "SONAR2")
      (value "ZX-XH2.54-4PZZ")
      (footprint "easyedapro:CONN-TH_4P-P2.50_4PIN")
      (fields (field (name "Manufacturer") "Megastar(兆星)"))
      (libsource (lib "easyedapro") (part "ZX-XH2.54-4PZZ"))
    )
    (comp (ref "SONAR3")
      (value "ZX-XH2.54-4PZZ")
      (footprint "easyedapro:CONN-TH_4P-P2.50_4PIN")
      (fields (field (name "Manufacturer") "Megastar(兆星)"))
      (libsource (lib "easyedapro") (part "ZX-XH2.54-4PZZ"))
    )
    (comp (ref "CN1")
      (value "ZX-XH2.54-3PZZ")
      (footprint "easyedapro:CONN-TH_3P-P2.54_2501S-3P")
      (fields (field (name "Manufacturer") "Megastar(兆星)"))
      (libsource (lib "easyedapro") (part "ZX-XH2.54-3PZZ"))
    )
    (comp (ref "CN2")
      (value "ZX-XH2.54-3PZZ")
      (footprint "easyedapro:CONN-TH_3P-P2.54_2501S-3P")
      (fields (field (name "Manufacturer") "Megastar(兆星)"))
      (libsource (lib "easyedapro") (part "ZX-XH2.54-3PZZ"))
    )
    (comp (ref "CN3")
      (value "ZX-XH2.54-3PZZ")
      (footprint "easyedapro:CONN-TH_3P-P2.54_2501S-3P")
      (fields (field (name "Manufacturer") "Megastar(兆星)"))
      (libsource (lib "easyedapro") (part "ZX-XH2.54-3PZZ"))
    )
    (comp (ref "CN50")
      (value "ZX-XH2.54-3PZZ")
      (footprint "easyedapro:CONN-TH_3P-P2.54_2501S-3P")
      (fields (field (name "Manufacturer") "Megastar(兆星)"))
      (libsource (lib "easyedapro") (part "ZX-XH2.54-3PZZ"))
    )
    (comp (ref "CN51")
      (value "ZX-XH2.54-3PZZ")
      (footprint "easyedapro:CONN-TH_3P-P2.54_2501S-3P")
      (fields (field (name "Manufacturer") "Megastar(兆星)"))
      (libsource (lib "easyedapro") (part "ZX-XH2.54-3PZZ"))
    )
    (comp (ref "CN52")
      (value "ZX-XH2.54-3PZZ")
      (footprint "easyedapro:CONN-TH_3P-P2.54_2501S-3P")
      (fields (field (name "Manufacturer") "Megastar(兆星)"))
      (libsource (lib "easyedapro") (part "ZX-XH2.54-3PZZ"))
    )
    (comp (ref "CN53")
      (value "ZX-XH2.54-3PZZ")
      (footprint "easyedapro:CONN-TH_3P-P2.54_2501S-3P")
      (fields (field (name "Manufacturer") "Megastar(兆星)"))
      (libsource (lib "easyedapro") (part "ZX-XH2.54-3PZZ"))
    )
    (comp (ref "CN54")
      (value "ZX-XH2.54-3PZZ")
      (footprint "easyedapro:CONN-TH_3P-P2.54_2501S-3P")
      (fields (field (name "Manufacturer") "Megastar(兆星)"))
      (libsource (lib "easyedapro") (part "ZX-XH2.54-3PZZ"))
    )
    (comp (ref "H1")
      (value "PZ254V-11-03P")
      (footprint "easyedapro:HDR-TH_3P-P2.54-V-M")
      (fields (field (name "Manufacturer") "XFCN(兴飞)"))
      (libsource (lib "easyedapro") (part "PZ254V-11-03P_C2937625"))
    )
    (comp (ref "P2")
      (value "WJ127-5.0-2P")
      (footprint "easyedapro:CONN-TH_2P-P5.00_CPC3703CTR")
      (fields (field (name "Manufacturer") "KANGNEX(康奈克斯电气)"))
      (libsource (lib "easyedapro") (part "WJ127-5.0-2P"))
    )
    (comp (ref "Q16")
      (value "BSS138")
      (footprint "easyedapro:SOT-23-3_L2.9-W1.6-P1.90-LS2.8-BR")
      (fields (field (name "Manufacturer") "TECH PUBLIC(台舟)"))
      (libsource (lib "easyedapro") (part "BSS138_C18212695"))
    )
    (comp (ref "Q19")
      (value "BSS138")
      (footprint "easyedapro:SOT-23-3_L2.9-W1.6-P1.90-LS2.8-BR")
      (fields (field (name "Manufacturer") "TECH PUBLIC(台舟)"))
      (libsource (lib "easyedapro") (part "BSS138_C18212695"))
    )
    (comp (ref "Q20")
      (value "BSS138")
      (footprint "easyedapro:SOT-23-3_L2.9-W1.6-P1.90-LS2.8-BR")
      (fields (field (name "Manufacturer") "TECH PUBLIC(台舟)"))
      (libsource (lib "easyedapro") (part "BSS138_C18212695"))
    )
    (comp (ref "Q21")
      (value "BSS138")
      (footprint "easyedapro:SOT-23-3_L2.9-W1.6-P1.90-LS2.8-BR")
      (fields (field (name "Manufacturer") "TECH PUBLIC(台舟)"))
      (libsource (lib "easyedapro") (part "BSS138_C18212695"))
    )
    (comp (ref "R39")
      (value "10kΩ")
      (footprint "easyedapro:R0603")
      (fields (field (name "Manufacturer Part") "RC0603FR-0710KL") (field (name "Manufacturer") "YAGEO(国巨)"))
      (libsource (lib "easyedapro") (part "RC0603FR-0710KL"))
    )
    (comp (ref "R40")
      (value "10kΩ")
      (footprint "easyedapro:R0603")
      (fields (field (name "Manufacturer Part") "RC0603FR-0710KL") (field (name "Manufacturer") "YAGEO(国巨)"))
      (libsource (lib "easyedapro") (part "RC0603FR-0710KL"))
    )
    (comp (ref "R41")
      (value "10kΩ")
      (footprint "easyedapro:R0603")
      (fields (field (name "Manufacturer Part") "RC0603FR-0710KL") (field (name "Manufacturer") "YAGEO(国巨)"))
      (libsource (lib "easyedapro") (part "RC0603FR-0710KL"))
    )
    (comp (ref "R42")
      (value "10kΩ")
      (footprint "easyedapro:R0603")
      (fields (field (name "Manufacturer Part") "RC0603FR-0710KL") (field (name "Manufacturer") "YAGEO(国巨)"))
      (libsource (lib "easyedapro") (part "RC0603FR-0710KL"))
    )
    (comp (ref "R43")
      (value "10kΩ")
      (footprint "easyedapro:R0603")
      (fields (field (name "Manufacturer Part") "RC0603FR-0710KL") (field (name "Manufacturer") "YAGEO(国巨)"))
      (libsource (lib "easyedapro") (part "RC0603FR-0710KL"))
    )
    (comp (ref "R44")
      (value "10kΩ")
      (footprint "easyedapro:R0603")
      (fields (field (name "Manufacturer Part") "RC0603FR-0710KL") (field (name "Manufacturer") "YAGEO(国巨)"))
      (libsource (lib "easyedapro") (part "RC0603FR-0710KL"))
    )
    (comp (ref "R45")
      (value "10kΩ")
      (footprint "easyedapro:R0603")
      (fields (field (name "Manufacturer Part") "RC0603FR-0710KL") (field (name "Manufacturer") "YAGEO(国巨)"))
      (libsource (lib "easyedapro") (part "RC0603FR-0710KL"))
    )
    (comp (ref "R46")
      (value "10kΩ")
      (footprint "easyedapro:R0603")
      (fields (field (name "Manufacturer Part") "RC0603FR-0710KL") (field (name "Manufacturer") "YAGEO(国巨)"))
      (libsource (lib "easyedapro") (part "RC0603FR-0710KL"))
    )
    (comp (ref "U19")
      (value "BX-PZ2.54-2-3PZZ")
      (footprint "easyedapro:HDR-TH_6P-P2.54-V-M-R2-C3-S2.54")
      (fields (field (name "Manufacturer") "Bossie(博锡)"))
      (libsource (lib "easyedapro") (part "BX-PZ2.54-2-3PZZ"))
    )
  )
  (nets
    (net (code "1") (name "3.3V") (class "Default")
      (node (ref "CN10") (pin "1") (pinfunction "1_1") (pintype "unspecified"))
      (node (ref "CN11") (pin "1") (pinfunction "1_1") (pintype "unspecified"))
      (node (ref "CN12") (pin "1") (pinfunction "1_1") (pintype "unspecified"))
      (node (ref "CN13") (pin "1") (pinfunction "1_1") (pintype "unspecified"))
      (node (ref "CN14") (pin "1") (pinfunction "1_1") (pintype "unspecified"))
      (node (ref "CN15") (pin "1") (pinfunction "1_1") (pintype "unspecified"))
      (node (ref "CN16") (pin "1") (pinfunction "1_1") (pintype "unspecified"))
      (node (ref "CN17") (pin "1") (pinfunction "1_1") (pintype "unspecified"))
      (node (ref "CN18") (pin "1") (pinfunction "1_1") (pintype "unspecified"))
      (node (ref "CN19") (pin "1") (pinfunction "1_1") (pintype "unspecified"))
      (node (ref "CN20") (pin "1") (pinfunction "1_1") (pintype "unspecified"))
      (node (ref "CN21") (pin "1") (pinfunction "1_1") (pintype "unspecified"))
      (node (ref "CN56") (pin "1") (pinfunction "1_1") (pintype "unspecified"))
      (node (ref "CN57") (pin "1") (pinfunction "1_1") (pintype "unspecified"))
      (node (ref "CN58") (pin "1") (pinfunction "1_1") (pintype "unspecified"))
      (node (ref "CN59") (pin "1") (pinfunction "1_1") (pintype "unspecified"))
      (node (ref "CN60") (pin "1") (pinfunction "1_1") (pintype "unspecified"))
      (node (ref "CN61") (pin "1") (pinfunction "1_1") (pintype "unspecified"))
      (node (ref "CN62") (pin "1") (pinfunction "1_1") (pintype "unspecified"))
      (node (ref "CN63") (pin "1") (pinfunction "1_1") (pintype "unspecified"))
      (node (ref "Q1") (pin "1") (pinfunction "G_1") (pintype "unspecified"))
      (node (ref "Q16") (pin "1") (pinfunction "G_1") (pintype "unspecified"))
      (node (ref "Q19") (pin "1") (pinfunction "G_1") (pintype "unspecified"))
      (node (ref "Q2") (pin "1") (pinfunction "G_1") (pintype "unspecified"))
      (node (ref "Q20") (pin "1") (pinfunction "G_1") (pintype "unspecified"))
      (node (ref "Q21") (pin "1") (pinfunction "G_1") (pintype "unspecified"))
      (node (ref "Q3") (pin "1") (pinfunction "G_1") (pintype "unspecified"))
      (node (ref "Q4") (pin "1") (pinfunction "G_1") (pintype "unspecified"))
      (node (ref "Q5") (pin "1") (pinfunction "G_1") (pintype "unspecified"))
      (node (ref "Q6") (pin "1") (pinfunction "G_1") (pintype "unspecified"))
      (node (ref "Q7") (pin "1") (pinfunction "G_1") (pintype "unspecified"))
      (node (ref "Q8") (pin "1") (pinfunction "G_1") (pintype "unspecified"))
      (node (ref "R1") (pin "1") (pinfunction "1_1") (pintype "input"))
      (node (ref "R10") (pin "2") (pinfunction "2_2") (pintype "input"))
      (node (ref "R11") (pin "2") (pinfunction "2_2") (pintype "input"))
      (node (ref "R12") (pin "2") (pinfunction "2_2") (pintype "input"))
      (node (ref "R13") (pin "2") (pinfunction "2_2") (pintype "input"))
      (node (ref "R14") (pin "2") (pinfunction "2_2") (pintype "input"))
      (node (ref "R15") (pin "2") (pinfunction "2_2") (pintype "input"))
      (node (ref "R16") (pin "2") (pinfunction "2_2") (pintype "input"))
      (node (ref "R17") (pin "2") (pinfunction "2_2") (pintype "input"))
      (node (ref "R18") (pin "2") (pinfunction "2_2") (pintype "input"))
      (node (ref "R2") (pin "1") (pinfunction "1_1") (pintype "input"))
      (node (ref "R20") (pin "1") (pinfunction "1_1") (pintype "input"))
      (node (ref "R22") (pin "2") (pinfunction "2_2") (pintype "input"))
      (node (ref "R24") (pin "1") (pinfunction "1_1") (pintype "input"))
      (node (ref "R26") (pin "2") (pinfunction "2_2") (pintype "input"))
      (node (ref "R28") (pin "1") (pinfunction "1_1") (pintype "input"))
      (node (ref "R3") (pin "1") (pinfunction "1_1") (pintype "input"))
      (node (ref "R30") (pin "2") (pinfunction "2_2") (pintype "input"))
      (node (ref "R32") (pin "1") (pinfunction "1_1") (pintype "input"))
      (node (ref "R34") (pin "2") (pinfunction "2_2") (pintype "input"))
      (node (ref "R39") (pin "2") (pinfunction "2_2") (pintype "input"))
      (node (ref "R4") (pin "1") (pinfunction "1_1") (pintype "input"))
      (node (ref "R41") (pin "2") (pinfunction "2_2") (pintype "input"))
      (node (ref "R43") (pin "2") (pinfunction "2_2") (pintype "input"))
      (node (ref "R45") (pin "2") (pinfunction "2_2") (pintype "input"))
      (node (ref "R5") (pin "1") (pinfunction "1_1") (pintype "input"))
      (node (ref "R6") (pin "1") (pinfunction "1_1") (pintype "input"))
      (node (ref "R7") (pin "1") (pinfunction "1_1") (pintype "input"))
      (node (ref "R8") (pin "1") (pinfunction "1_1") (pintype "input"))
      (node (ref "R9") (pin "2") (pinfunction "2_2") (pintype "input"))
      (node (ref "U1") (pin "15") (pinfunction "3.3V_15") (pintype "unspecified"))
      (node (ref "U1") (pin "46") (pinfunction "3.3V_46") (pintype "unspecified"))
      (node (ref "U19") (pin "1") (pinfunction "1_1") (pintype "unspecified"))
      (node (ref "U2") (pin "24") (pinfunction "VCC_24") (pintype "unspecified"))
      (node (ref "U43") (pin "3") (pinfunction "3_3") (pintype "unspecified"))
      (node (ref "U44") (pin "15") (pinfunction "15_15") (pintype "unspecified"))
      (node (ref "U5") (pin "1") (pinfunction "1_1") (pintype "unspecified"))
      (node (ref "U6") (pin "1") (pinfunction "1_1") (pintype "unspecified"))
    )
    (net (code "2") (name "5V") (class "Default")
      (node (ref "H1") (pin "1") (pinfunction "1_1") (pintype "unspecified"))
      (node (ref "P1") (pin "2") (pinfunction "2_2") (pintype "input"))
      (node (ref "R19") (pin "1") (pinfunction "1_1") (pintype "input"))
      (node (ref "R21") (pin "2") (pinfunction "2_2") (pintype "input"))
      (node (ref "R23") (pin "1") (pinfunction "1_1") (pintype "input"))
      (node (ref "R25") (pin "2") (pinfunction "2_2") (pintype "input"))
      (node (ref "R27") (pin "1") (pinfunction "1_1") (pintype "input"))
      (node (ref "R29") (pin "2") (pinfunction "2_2") (pintype "input"))
      (node (ref "R31") (pin "1") (pinfunction "1_1") (pintype "input"))
      (node (ref "R33") (pin "2") (pinfunction "2_2") (pintype "input"))
      (node (ref "SONAR0") (pin "1") (pinfunction "1_1") (pintype "unspecified"))
      (node (ref "SONAR1") (pin "1") (pinfunction "1_1") (pintype "unspecified"))
      (node (ref "SONAR2") (pin "1") (pinfunction "1_1") (pintype "unspecified"))
      (node (ref "SONAR3") (pin "1") (pinfunction "1_1") (pintype "unspecified"))
      (node (ref "U1") (pin "48") (pinfunction "VIN_48") (pintype "unspecified"))
      (node (ref "U19") (pin "3") (pinfunction "3_3") (pintype "unspecified"))
      (node (ref "U4") (pin "1") (pinfunction "1_1") (pintype "unspecified"))
      (node (ref "U43") (pin "1") (pinfunction "1_1") (pintype "unspecified"))
      (node (ref "U8") (pin "1") (pinfunction "1_1") (pintype "unspecified"))
    )
    (net (code "3") (name "A10") (class "Default")
      (node (ref "CN63") (pin "3") (pinfunction "3_3") (pintype "unspecified"))
      (node (ref "U1") (pin "16") (pinfunction "SCL2/TX6/A10_16") (pintype "unspecified"))
      (node (ref "U44") (pin "16") (pinfunction "16_16") (pintype "unspecified"))
    )
    (net (code "4") (name "A11") (class "Default")
      (node (ref "CN62") (pin "3") (pinfunction "3_3") (pintype "unspecified"))
      (node (ref "U1") (pin "17") (pinfunction "SDA2/RX6/A11_17") (pintype "unspecified"))
      (node (ref "U44") (pin "17") (pinfunction "17_17") (pintype "unspecified"))
    )
    (net (code "5") (name "A12") (class "Default")
      (node (ref "CN61") (pin "3") (pinfunction "3_3") (pintype "unspecified"))
      (node (ref "U1") (pin "18") (pinfunction "MOSI1/A12_18") (pintype "unspecified"))
      (node (ref "U44") (pin "18") (pinfunction "18_18") (pintype "unspecified"))
    )
    (net (code "6") (name "A13") (class "Default")
      (node (ref "CN60") (pin "3") (pinfunction "3_3") (pintype "unspecified"))
      (node (ref "U1") (pin "19") (pinfunction "SCK1/A13_19") (pintype "unspecified"))
      (node (ref "U44") (pin "19") (pinfunction "19_19") (pintype "unspecified"))
    )
    (net (code "7") (name "A14") (class "Default")
      (node (ref "CN59") (pin "3") (pinfunction "3_3") (pintype "unspecified"))
      (node (ref "U1") (pin "30") (pinfunction "INN/CS1/A14_30") (pintype "unspecified"))
      (node (ref "U43") (pin "19") (pinfunction "19_19") (pintype "unspecified"))
    )
    (net (code "8") (name "A15") (class "Default")
      (node (ref "CN58") (pin "3") (pinfunction "3_3") (pintype "unspecified"))
      (node (ref "U1") (pin "31") (pinfunction "OUT1A/MISO1/A15_31") (pintype "unspecified"))
      (node (ref "U43") (pin "18") (pinfunction "18_18") (pintype "unspecified"))
    )
    (net (code "9") (name "A16") (class "Default")
      (node (ref "CN57") (pin "3") (pinfunction "3_3") (pintype "unspecified"))
      (node (ref "U1") (pin "32") (pinfunction "A16_32") (pintype "unspecified"))
      (node (ref "U43") (pin "17") (pinfunction "17_17") (pintype "unspecified"))
    )
    (net (code "10") (name "A17") (class "Default")
      (node (ref "CN56") (pin "3") (pinfunction "3_3") (pintype "unspecified"))
      (node (ref "U1") (pin "33") (pinfunction "A17_33") (pintype "unspecified"))
      (node (ref "U43") (pin "16") (pinfunction "16_16") (pintype "unspecified"))
    )
    (net (code "11") (name "BCLK2") (class "Default")
      (node (ref "CN50") (pin "3") (pinfunction "3_3") (pintype "unspecified"))
      (node (ref "U1") (pin "6") (pinfunction "BCLK2_6") (pintype "unspecified"))
      (node (ref "U44") (pin "6") (pinfunction "6_6") (pintype "unspecified"))
    )
    (net (code "12") (name "CRX1") (class "Default")
      (node (ref "CN10") (pin "3") (pinfunction "3_3") (pintype "unspecified"))
      (node (ref "U1") (pin "45") (pinfunction "CRX1/A9_45") (pintype "unspecified"))
      (node (ref "U43") (pin "4") (pinfunction "4_4") (pintype "unspecified"))
    )
    (net (code "13") (name "CRX3") (class "Default")
      (node (ref "U1") (pin "22") (pinfunction "CRX3_22") (pintype "unspecified"))
      (node (ref "U44") (pin "22") (pinfunction "22_22") (pintype "unspecified"))
      (node (ref "U5") (pin "5") (pinfunction "5_5") (pintype "unspecified"))
    )
    (net (code "14") (name "CS") (class "Default")
      (node (ref "U1") (pin "12") (pinfunction "MQSR/CS_12") (pintype "unspecified"))
      (node (ref "U4") (pin "6") (pinfunction "6_6") (pintype "unspecified"))
      (node (ref "U44") (pin "12") (pinfunction "12_12") (pintype "unspecified"))
    )
    (net (code "15") (name "CTX1") (class "Default")
      (node (ref "CN10") (pin "4") (pinfunction "4_4") (pintype "unspecified"))
      (node (ref "U1") (pin "44") (pinfunction "CTX1/A8_44") (pintype "unspecified"))
      (node (ref "U43") (pin "5") (pinfunction "5_5") (pintype "unspecified"))
    )
    (net (code "16") (name "CTX3") (class "Default")
      (node (ref "U1") (pin "23") (pinfunction "CTX3_23") (pintype "unspecified"))
      (node (ref "U44") (pin "23") (pinfunction "23_23") (pintype "unspecified"))
      (node (ref "U6") (pin "5") (pinfunction "5_5") (pintype "unspecified"))
    )
    (net (code "17") (name "ECHO0") (class "Default")
      (node (ref "Q2") (pin "3") (pinfunction "D_3") (pintype "unspecified"))
      (node (ref "R22") (pin "1") (pinfunction "1_1") (pintype "input"))
      (node (ref "U1") (pin "25") (pinfunction "MCLK2_25") (pintype "unspecified"))
      (node (ref "U43") (pin "24") (pinfunction "24_24") (pintype "unspecified"))
    )
    (net (code "18") (name "ECHO1") (class "Default")
      (node (ref "Q4") (pin "3") (pinfunction "D_3") (pintype "unspecified"))
      (node (ref "R26") (pin "1") (pinfunction "1_1") (pintype "input"))
      (node (ref "U1") (pin "27") (pinfunction "TX8_27") (pintype "unspecified"))
      (node (ref "U43") (pin "22") (pinfunction "22_22") (pintype "unspecified"))
    )
    (net (code "19") (name "ECHO2") (class "Default")
      (node (ref "Q6") (pin "3") (pinfunction "D_3") (pintype "unspecified"))
      (node (ref "R30") (pin "1") (pinfunction "1_1") (pintype "input"))
      (node (ref "U1") (pin "29") (pinfunction "CS_29") (pintype "unspecified"))
      (node (ref "U43") (pin "20") (pinfunction "20_20") (pintype "unspecified"))
    )
    (net (code "20") (name "ECHO3") (class "Default")
      (node (ref "Q8") (pin "3") (pinfunction "D_3") (pintype "unspecified"))
      (node (ref "R34") (pin "1") (pinfunction "1_1") (pintype "input"))
      (node (ref "U1") (pin "37") (pinfunction "RX3/A1_37") (pintype "unspecified"))
      (node (ref "U43") (pin "12") (pinfunction "12_12") (pintype "unspecified"))
    )
    (net (code "21") (name "GND") (class "Default")
      (node (ref "CN1") (pin "2") (pinfunction "2_2") (pintype "unspecified"))
      (node (ref "CN10") (pin "2") (pinfunction "2_2") (pintype "unspecified"))
      (node (ref "CN11") (pin "2") (pinfunction "2_2") (pintype "unspecified"))
      (node (ref "CN12") (pin "2") (pinfunction "2_2") (pintype "unspecified"))
      (node (ref "CN13") (pin "2") (pinfunction "2_2") (pintype "unspecified"))
      (node (ref "CN14") (pin "2") (pinfunction "2_2") (pintype "unspecified"))
      (node (ref "CN15") (pin "2") (pinfunction "2_2") (pintype "unspecified"))
      (node (ref "CN16") (pin "2") (pinfunction "2_2") (pintype "unspecified"))
      (node (ref "CN17") (pin "2") (pinfunction "2_2") (pintype "unspecified"))
      (node (ref "CN18") (pin "2") (pinfunction "2_2") (pintype "unspecified"))
      (node (ref "CN19") (pin "2") (pinfunction "2_2") (pintype "unspecified"))
      (node (ref "CN2") (pin "2") (pinfunction "2_2") (pintype "unspecified"))
      (node (ref "CN20") (pin "2") (pinfunction "2_2") (pintype "unspecified"))
      (node (ref "CN21") (pin "2") (pinfunction "2_2") (pintype "unspecified"))
      (node (ref "CN3") (pin "2") (pinfunction "2_2") (pintype "unspecified"))
      (node (ref "CN50") (pin "2") (pinfunction "2_2") (pintype "unspecified"))
      (node (ref "CN51") (pin "2") (pinfunction "2_2") (pintype "unspecified"))
      (node (ref "CN52") (pin "2") (pinfunction "2_2") (pintype "unspecified"))
      (node (ref "CN53") (pin "2") (pinfunction "2_2") (pintype "unspecified"))
      (node (ref "CN54") (pin "2") (pinfunction "2_2") (pintype "unspecified"))
      (node (ref "CN56") (pin "2") (pinfunction "2_2") (pintype "unspecified"))
      (node (ref "CN57") (pin "2") (pinfunction "2_2") (pintype "unspecified"))
      (node (ref "CN58") (pin "2") (pinfunction "2_2") (pintype "unspecified"))
      (node (ref "CN59") (pin "2") (pinfunction "2_2") (pintype "unspecified"))
      (node (ref "CN60") (pin "2") (pinfunction "2_2") (pintype "unspecified"))
      (node (ref "CN61") (pin "2") (pinfunction "2_2") (pintype "unspecified"))
      (node (ref "CN62") (pin "2") (pinfunction "2_2") (pintype "unspecified"))
      (node (ref "CN63") (pin "2") (pinfunction "2_2") (pintype "unspecified"))
      (node (ref "H18") (pin "1") (pinfunction "1_1") (pintype "unspecified"))
      (node (ref "H18") (pin "3") (pinfunction "3_3") (pintype "unspecified"))
      (node (ref "P1") (pin "1") (pinfunction "1_1") (pintype "input"))
      (node (ref "P2") (pin "1") (pinfunction "1_1") (pintype "input"))
      (node (ref "SONAR0") (pin "2") (pinfunction "2_2") (pintype "unspecified"))
      (node (ref "SONAR1") (pin "2") (pinfunction "2_2") (pintype "unspecified"))
      (node (ref "SONAR2") (pin "2") (pinfunction "2_2") (pintype "unspecified"))
      (node (ref "SONAR3") (pin "2") (pinfunction "2_2") (pintype "unspecified"))
      (node (ref "U1") (pin "1") (pinfunction "GND_1") (pintype "unspecified"))
      (node (ref "U1") (pin "34") (pinfunction "GND_34") (pintype "unspecified"))
      (node (ref "U1") (pin "47") (pinfunction "GND_47") (pintype "unspecified"))
      (node (ref "U2") (pin "1") (pinfunction "A0_1") (pintype "unspecified"))
      (node (ref "U2") (pin "12") (pinfunction "GND_12") (pintype "unspecified"))
      (node (ref "U2") (pin "2") (pinfunction "A1_2") (pintype "unspecified"))
      (node (ref "U2") (pin "21") (pinfunction "A2_21") (pintype "unspecified"))
      (node (ref "U4") (pin "2") (pinfunction "2_2") (pintype "unspecified"))
      (node (ref "U43") (pin "15") (pinfunction "15_15") (pintype "unspecified"))
      (node (ref "U43") (pin "2") (pinfunction "2_2") (pintype "unspecified"))
      (node (ref "U44") (pin "1") (pinfunction "1_1") (pintype "unspecified"))
      (node (ref "U48") (pin "3") (pinfunction "3_3") (pintype "input"))
      (node (ref "U5") (pin "2") (pinfunction "2_2") (pintype "unspecified"))
      (node (ref "U6") (pin "2") (pinfunction "2_2") (pintype "unspecified"))
      (node (ref "U8") (pin "2") (pinfunction "2_2") (pintype "unspecified"))
    )
    (net (code "22") (name "I2CRESET") (class "Default")
      (node (ref "U1") (pin "10") (pinfunction "IN1/TX2_10") (pintype "unspecified"))
      (node (ref "U2") (pin "3") (pinfunction "RESET#_3") (pintype "unspecified"))
      (node (ref "U44") (pin "10") (pinfunction "10_10") (pintype "unspecified"))
    )
    (net (code "23") (name "IN2") (class "Default")
      (node (ref "CN51") (pin "3") (pinfunction "3_3") (pintype "unspecified"))
      (node (ref "U1") (pin "7") (pinfunction "IN2_7") (pintype "unspecified"))
      (node (ref "U44") (pin "7") (pinfunction "7_7") (pintype "unspecified"))
    )
    (net (code "24") (name "LRCLK2") (class "Default")
      (node (ref "Q16") (pin "2") (pinfunction "S_2") (pintype "unspecified"))
      (node (ref "R39") (pin "1") (pinfunction "1_1") (pintype "input"))
      (node (ref "U1") (pin "5") (pinfunction "LRCLK2_5") (pintype "unspecified"))
      (node (ref "U44") (pin "5") (pinfunction "5_5") (pintype "unspecified"))
    )
    (net (code "25") (name "MISO") (class "Default")
      (node (ref "U1") (pin "14") (pinfunction "MQSL/MISO_14") (pintype "unspecified"))
      (node (ref "U4") (pin "4") (pinfunction "4_4") (pintype "unspecified"))
      (node (ref "U44") (pin "14") (pinfunction "14_14") (pintype "unspecified"))
      (node (ref "U8") (pin "4") (pinfunction "4_4") (pintype "unspecified"))
    )
    (net (code "26") (name "MOSI") (class "Default")
      (node (ref "U1") (pin "13") (pinfunction "CTX1/MOSI_13") (pintype "unspecified"))
      (node (ref "U4") (pin "3") (pinfunction "3_3") (pintype "unspecified"))
      (node (ref "U44") (pin "13") (pinfunction "13_13") (pintype "unspecified"))
      (node (ref "U8") (pin "3") (pinfunction "3_3") (pintype "unspecified"))
    )
    (net (code "27") (name "Net-(CN1-Pad1)") (class "Default")
      (node (ref "CN1") (pin "1") (pinfunction "1_1") (pintype "unspecified"))
      (node (ref "CN2") (pin "1") (pinfunction "1_1") (pintype "unspecified"))
      (node (ref "CN3") (pin "1") (pinfunction "1_1") (pintype "unspecified"))
      (node (ref "CN54") (pin "1") (pinfunction "1_1") (pintype "unspecified"))
      (node (ref "R40") (pin "2") (pinfunction "2_2") (pintype "input"))
      (node (ref "R42") (pin "2") (pinfunction "2_2") (pintype "input"))
      (node (ref "R44") (pin "2") (pinfunction "2_2") (pintype "input"))
      (node (ref "R46") (pin "2") (pinfunction "2_2") (pintype "input"))
      (node (ref "U19") (pin "2") (pinfunction "2_2") (pintype "unspecified"))
      (node (ref "U19") (pin "4") (pinfunction "4_4") (pintype "unspecified"))
      (node (ref "U19") (pin "6") (pinfunction "6_6") (pintype "unspecified"))
    )
    (net (code "28") (name "Net-(CN50-Pad1)") (class "Default")
      (node (ref "CN50") (pin "1") (pinfunction "1_1") (pintype "unspecified"))
      (node (ref "CN51") (pin "1") (pinfunction "1_1") (pintype "unspecified"))
      (node (ref "CN52") (pin "1") (pinfunction "1_1") (pintype "unspecified"))
      (node (ref "CN53") (pin "1") (pinfunction "1_1") (pintype "unspecified"))
      (node (ref "H1") (pin "2") (pinfunction "2_2") (pintype "unspecified"))
    )
    (net (code "29") (name "Net-(H1-Pad3)") (class "Default")
      (node (ref "H1") (pin "3") (pinfunction "3_3") (pintype "unspecified"))
      (node (ref "P2") (pin "2") (pinfunction "2_2") (pintype "input"))
      (node (ref "U19") (pin "5") (pinfunction "5_5") (pintype "unspecified"))
    )
    (net (code "30") (name "Net-(Q1-D)") (class "Default")
      (node (ref "Q1") (pin "3") (pinfunction "D_3") (pintype "unspecified"))
      (node (ref "R19") (pin "2") (pinfunction "2_2") (pintype "input"))
      (node (ref "SONAR0") (pin "3") (pinfunction "3_3") (pintype "unspecified"))
    )
    (net (code "31") (name "Net-(Q2-S)") (class "Default")
      (node (ref "Q2") (pin "2") (pinfunction "S_2") (pintype "unspecified"))
      (node (ref "R21") (pin "1") (pinfunction "1_1") (pintype "input"))
      (node (ref "SONAR0") (pin "4") (pinfunction "4_4") (pintype "unspecified"))
    )
    (net (code "32") (name "Net-(Q3-D)") (class "Default")
      (node (ref "Q3") (pin "3") (pinfunction "D_3") (pintype "unspecified"))
      (node (ref "R23") (pin "2") (pinfunction "2_2") (pintype "input"))
      (node (ref "SONAR1") (pin "3") (pinfunction "3_3") (pintype "unspecified"))
    )
    (net (code "33") (name "Net-(Q4-S)") (class "Default")
      (node (ref "Q4") (pin "2") (pinfunction "S_2") (pintype "unspecified"))
      (node (ref "R25") (pin "1") (pinfunction "1_1") (pintype "input"))
      (node (ref "SONAR1") (pin "4") (pinfunction "4_4") (pintype "unspecified"))
    )
    (net (code "34") (name "Net-(Q5-D)") (class "Default")
      (node (ref "Q5") (pin "3") (pinfunction "D_3") (pintype "unspecified"))
      (node (ref "R27") (pin "2") (pinfunction "2_2") (pintype "input"))
      (node (ref "SONAR2") (pin "3") (pinfunction "3_3") (pintype "unspecified"))
    )
    (net (code "35") (name "Net-(Q6-S)") (class "Default")
      (node (ref "Q6") (pin "2") (pinfunction "S_2") (pintype "unspecified"))
      (node (ref "R29") (pin "1") (pinfunction "1_1") (pintype "input"))
      (node (ref "SONAR2") (pin "4") (pinfunction "4_4") (pintype "unspecified"))
    )
    (net (code "36") (name "Net-(Q7-D)") (class "Default")
      (node (ref "Q7") (pin "3") (pinfunction "D_3") (pintype "unspecified"))
      (node (ref "R31") (pin "2") (pinfunction "2_2") (pintype "input"))
      (node (ref "SONAR3") (pin "3") (pinfunction "3_3") (pintype "unspecified"))
    )
    (net (code "37") (name "Net-(Q8-S)") (class "Default")
      (node (ref "Q8") (pin "2") (pinfunction "S_2") (pintype "unspecified"))
      (node (ref "R33") (pin "1") (pinfunction "1_1") (pintype "input"))
      (node (ref "SONAR3") (pin "4") (pinfunction "4_4") (pintype "unspecified"))
    )
    (net (code "38") (name "Net-(Q16-D)") (class "Default")
      (node (ref "CN1") (pin "3") (pinfunction "3_3") (pintype "unspecified"))
      (node (ref "Q16") (pin "3") (pinfunction "D_3") (pintype "unspecified"))
      (node (ref "R40") (pin "1") (pinfunction "1_1") (pintype "input"))
    )
    (net (code "39") (name "Net-(Q19-D)") (class "Default")
      (node (ref "CN2") (pin "3") (pinfunction "3_3") (pintype "unspecified"))
      (node (ref "Q19") (pin "3") (pinfunction "D_3") (pintype "unspecified"))
      (node (ref "R42") (pin "1") (pinfunction "1_1") (pintype "input"))
    )
    (net (code "40") (name "Net-(Q20-D)") (class "Default")
      (node (ref "CN54") (pin "3") (pinfunction "3_3") (pintype "unspecified"))
      (node (ref "Q20") (pin "3") (pinfunction "D_3") (pintype "unspecified"))
      (node (ref "R44") (pin "1") (pinfunction "1_1") (pintype "input"))
    )
    (net (code "41") (name "Net-(Q21-D)") (class "Default")
      (node (ref "CN3") (pin "3") (pinfunction "3_3") (pintype "unspecified"))
      (node (ref "Q21") (pin "3") (pinfunction "D_3") (pintype "unspecified"))
      (node (ref "R46") (pin "1") (pinfunction "1_1") (pintype "input"))
    )
    (net (code "42") (name "Net-(U2-SC0)") (class "Default")
      (node (ref "CN14") (pin "3") (pinfunction "3_3") (pintype "unspecified"))
      (node (ref "R2") (pin "2") (pinfunction "2_2") (pintype "input"))
      (node (ref "U2") (pin "5") (pinfunction "SC0_5") (pintype "unspecified"))
    )
    (net (code "43") (name "Net-(U2-SC1)") (class "Default")
      (node (ref "CN15") (pin "3") (pinfunction "3_3") (pintype "unspecified"))
      (node (ref "R4") (pin "2") (pinfunction "2_2") (pintype "input"))
      (node (ref "U2") (pin "7") (pinfunction "SC1_7") (pintype "unspecified"))
    )
    (net (code "44") (name "Net-(U2-SC2)") (class "Default")
      (node (ref "CN16") (pin "3") (pinfunction "3_3") (pintype "unspecified"))
      (node (ref "R6") (pin "2") (pinfunction "2_2") (pintype "input"))
      (node (ref "U2") (pin "9") (pinfunction "SC2_9") (pintype "unspecified"))
    )
    (net (code "45") (name "Net-(U2-SC3)") (class "Default")
      (node (ref "CN17") (pin "3") (pinfunction "3_3") (pintype "unspecified"))
      (node (ref "R8") (pin "2") (pinfunction "2_2") (pintype "input"))
      (node (ref "U2") (pin "11") (pinfunction "SC3_11") (pintype "unspecified"))
    )
    (net (code "46") (name "Net-(U2-SC4)") (class "Default")
      (node (ref "CN18") (pin "3") (pinfunction "3_3") (pintype "unspecified"))
      (node (ref "R15") (pin "1") (pinfunction "1_1") (pintype "input"))
      (node (ref "U2") (pin "14") (pinfunction "SC4_14") (pintype "unspecified"))
    )
    (net (code "47") (name "Net-(U2-SC5)") (class "Default")
      (node (ref "CN19") (pin "3") (pinfunction "3_3") (pintype "unspecified"))
      (node (ref "R13") (pin "1") (pinfunction "1_1") (pintype "input"))
      (node (ref "U2") (pin "16") (pinfunction "SC5_16") (pintype "unspecified"))
    )
    (net (code "48") (name "Net-(U2-SC6)") (class "Default")
      (node (ref "CN20") (pin "3") (pinfunction "3_3") (pintype "unspecified"))
      (node (ref "R11") (pin "1") (pinfunction "1_1") (pintype "input"))
      (node (ref "U2") (pin "18") (pinfunction "SC6_18") (pintype "unspecified"))
    )
    (net (code "49") (name "Net-(U2-SC7)") (class "Default")
      (node (ref "CN21") (pin "3") (pinfunction "3_3") (pintype "unspecified"))
      (node (ref "R9") (pin "1") (pinfunction "1_1") (pintype "input"))
      (node (ref "U2") (pin "20") (pinfunction "SC7_20") (pintype "unspecified"))
    )
    (net (code "50") (name "Net-(U2-SD0)") (class "Default")
      (node (ref "CN14") (pin "4") (pinfunction "4_4") (pintype "unspecified"))
      (node (ref "R1") (pin "2") (pinfunction "2_2") (pintype "input"))
      (node (ref "U2") (pin "4") (pinfunction "SD0_4") (pintype "unspecified"))
    )
    (net (code "51") (name "Net-(U2-SD1)") (class "Default")
      (node (ref "CN15") (pin "4") (pinfunction "4_4") (pintype "unspecified"))
      (node (ref "R3") (pin "2") (pinfunction "2_2") (pintype "input"))
      (node (ref "U2") (pin "6") (pinfunction "SD1_6") (pintype "unspecified"))
    )
    (net (code "52") (name "Net-(U2-SD2)") (class "Default")
      (node (ref "CN16") (pin "4") (pinfunction "4_4") (pintype "unspecified"))
      (node (ref "R5") (pin "2") (pinfunction "2_2") (pintype "input"))
      (node (ref "U2") (pin "8") (pinfunction "SD2_8") (pintype "unspecified"))
    )
    (net (code "53") (name "Net-(U2-SD3)") (class "Default")
      (node (ref "CN17") (pin "4") (pinfunction "4_4") (pintype "unspecified"))
      (node (ref "R7") (pin "2") (pinfunction "2_2") (pintype "input"))
      (node (ref "U2") (pin "10") (pinfunction "SD3_10") (pintype "unspecified"))
    )
    (net (code "54") (name "Net-(U2-SD4)") (class "Default")
      (node (ref "CN18") (pin "4") (pinfunction "4_4") (pintype "unspecified"))
      (node (ref "R16") (pin "1") (pinfunction "1_1") (pintype "input"))
      (node (ref "U2") (pin "13") (pinfunction "SD4_13") (pintype "unspecified"))
    )
    (net (code "55") (name "Net-(U2-SD5)") (class "Default")
      (node (ref "CN19") (pin "4") (pinfunction "4_4") (pintype "unspecified"))
      (node (ref "R14") (pin "1") (pinfunction "1_1") (pintype "input"))
      (node (ref "U2") (pin "15") (pinfunction "SD5_15") (pintype "unspecified"))
    )
    (net (code "56") (name "Net-(U2-SD6)") (class "Default")
      (node (ref "CN20") (pin "4") (pinfunction "4_4") (pintype "unspecified"))
      (node (ref "R12") (pin "1") (pinfunction "1_1") (pintype "input"))
      (node (ref "U2") (pin "17") (pinfunction "SD6_17") (pintype "unspecified"))
    )
    (net (code "57") (name "Net-(U2-SD7)") (class "Default")
      (node (ref "CN21") (pin "4") (pinfunction "4_4") (pintype "unspecified"))
      (node (ref "R10") (pin "1") (pinfunction "1_1") (pintype "input"))
      (node (ref "U2") (pin "19") (pinfunction "SD7_19") (pintype "unspecified"))
    )
    (net (code "58") (name "ON_OFF") (class "Default")
      (node (ref "H18") (pin "4") (pinfunction "4_4") (pintype "unspecified"))
      (node (ref "U48") (pin "1") (pinfunction "1_1") (pintype "input"))
    )
    (net (code "59") (name "OUT1A") (class "Default")
      (node (ref "CN53") (pin "3") (pinfunction "3_3") (pintype "unspecified"))
      (node (ref "U1") (pin "9") (pinfunction "OUT1A/RX2_9") (pintype "unspecified"))
      (node (ref "U44") (pin "9") (pinfunction "9_9") (pintype "unspecified"))
    )
    (net (code "60") (name "OUT1C") (class "Default")
      (node (ref "U1") (pin "11") (pinfunction "OUT1C_11") (pintype "unspecified"))
      (node (ref "U44") (pin "11") (pinfunction "11_11") (pintype "unspecified"))
      (node (ref "U8") (pin "6") (pinfunction "6_6") (pintype "unspecified"))
    )
    (net (code "61") (name "OUT1D") (class "Default")
      (node (ref "CN52") (pin "3") (pinfunction "3_3") (pintype "unspecified"))
      (node (ref "U1") (pin "8") (pinfunction "OUT1D_8") (pintype "unspecified"))
      (node (ref "U44") (pin "8") (pinfunction "8_8") (pintype "unspecified"))
    )
    (net (code "62") (name "OUT2") (class "Default")
      (node (ref "Q19") (pin "2") (pinfunction "S_2") (pintype "unspecified"))
      (node (ref "R41") (pin "1") (pinfunction "1_1") (pintype "input"))
      (node (ref "U1") (pin "4") (pinfunction "OUT2_4") (pintype "unspecified"))
      (node (ref "U44") (pin "4") (pinfunction "4_4") (pintype "unspecified"))
    )
    (net (code "63") (name "PROGRAM") (class "Default")
      (node (ref "H18") (pin "2") (pinfunction "2_2") (pintype "unspecified"))
      (node (ref "U48") (pin "2") (pinfunction "2_2") (pintype "input"))
    )
    (net (code "64") (name "RX1") (class "Default")
      (node (ref "Q21") (pin "2") (pinfunction "S_2") (pintype "unspecified"))
      (node (ref "R45") (pin "1") (pinfunction "1_1") (pintype "input"))
      (node (ref "U1") (pin "2") (pinfunction "CRX2/CS1/RX1_2") (pintype "unspecified"))
      (node (ref "U44") (pin "2") (pinfunction "2_2") (pintype "unspecified"))
    )
    (net (code "65") (name "RX4") (class "Default")
      (node (ref "U1") (pin "38") (pinfunction "RX4/A2_38") (pintype "unspecified"))
      (node (ref "U43") (pin "11") (pinfunction "11_11") (pintype "unspecified"))
      (node (ref "U6") (pin "3") (pinfunction "3_3") (pintype "unspecified"))
    )
    (net (code "66") (name "RX5") (class "Default")
      (node (ref "CN13") (pin "3") (pinfunction "3_3") (pintype "unspecified"))
      (node (ref "U1") (pin "43") (pinfunction "RX5/A7_43") (pintype "unspecified"))
      (node (ref "U43") (pin "6") (pinfunction "6_6") (pintype "unspecified"))
    )
    (net (code "67") (name "RX7") (class "Default")
      (node (ref "U1") (pin "20") (pinfunction "RX7_20") (pintype "unspecified"))
      (node (ref "U44") (pin "20") (pinfunction "20_20") (pintype "unspecified"))
      (node (ref "U5") (pin "3") (pinfunction "3_3") (pintype "unspecified"))
    )
    (net (code "68") (name "SCK") (class "Default")
      (node (ref "U1") (pin "35") (pinfunction "SCK_35") (pintype "unspecified"))
      (node (ref "U4") (pin "5") (pinfunction "5_5") (pintype "unspecified"))
      (node (ref "U43") (pin "14") (pinfunction "14_14") (pintype "unspecified"))
      (node (ref "U8") (pin "5") (pinfunction "5_5") (pintype "unspecified"))
    )
    (net (code "69") (name "SCL") (class "Default")
      (node (ref "CN11") (pin "3") (pinfunction "3_3") (pintype "unspecified"))
      (node (ref "CN12") (pin "3") (pinfunction "3_3") (pintype "unspecified"))
      (node (ref "R17") (pin "1") (pinfunction "1_1") (pintype "input"))
      (node (ref "U1") (pin "41") (pinfunction "A5_41") (pintype "unspecified"))
      (node (ref "U2") (pin "22") (pinfunction "SCL_22") (pintype "unspecified"))
      (node (ref "U43") (pin "8") (pinfunction "8_8") (pintype "unspecified"))
    )
    (net (code "70") (name "SDA") (class "Default")
      (node (ref "CN11") (pin "4") (pinfunction "4_4") (pintype "unspecified"))
      (node (ref "CN12") (pin "4") (pinfunction "4_4") (pintype "unspecified"))
      (node (ref "R18") (pin "1") (pinfunction "1_1") (pintype "input"))
      (node (ref "U1") (pin "40") (pinfunction "A4_40") (pintype "unspecified"))
      (node (ref "U2") (pin "23") (pinfunction "SDA_23") (pintype "unspecified"))
      (node (ref "U43") (pin "9") (pinfunction "9_9") (pintype "unspecified"))
    )
    (net (code "71") (name "TRIG0") (class "Default")
      (node (ref "Q1") (pin "2") (pinfunction "S_2") (pintype "unspecified"))
      (node (ref "R20") (pin "2") (pinfunction "2_2") (pintype "input"))
      (node (ref "U1") (pin "24") (pinfunction "OUT1B_24") (pintype "unspecified"))
      (node (ref "U44") (pin "24") (pinfunction "24_24") (pintype "unspecified"))
    )
    (net (code "72") (name "TRIG1") (class "Default")
      (node (ref "Q3") (pin "2") (pinfunction "S_2") (pintype "unspecified"))
      (node (ref "R24") (pin "2") (pinfunction "2_2") (pintype "input"))
      (node (ref "U1") (pin "26") (pinfunction "RX8_26") (pintype "unspecified"))
      (node (ref "U43") (pin "23") (pinfunction "23_23") (pintype "unspecified"))
    )
    (net (code "73") (name "TRIG2") (class "Default")
      (node (ref "Q5") (pin "2") (pinfunction "S_2") (pintype "unspecified"))
      (node (ref "R28") (pin "2") (pinfunction "2_2") (pintype "input"))
      (node (ref "U1") (pin "28") (pinfunction "CS_28") (pintype "unspecified"))
      (node (ref "U43") (pin "21") (pinfunction "21_21") (pintype "unspecified"))
    )
    (net (code "74") (name "TRIG3") (class "Default")
      (node (ref "Q7") (pin "2") (pinfunction "S_2") (pintype "unspecified"))
      (node (ref "R32") (pin "2") (pinfunction "2_2") (pintype "input"))
      (node (ref "U1") (pin "36") (pinfunction "TX3/A0_36") (pintype "unspecified"))
      (node (ref "U43") (pin "13") (pinfunction "13_13") (pintype "unspecified"))
    )
    (net (code "75") (name "TX1") (class "Default")
      (node (ref "Q20") (pin "2") (pinfunction "S_2") (pintype "unspecified"))
      (node (ref "R43") (pin "1") (pinfunction "1_1") (pintype "input"))
      (node (ref "U1") (pin "3") (pinfunction "CTX2/MISO1/TX1_3") (pintype "unspecified"))
      (node (ref "U44") (pin "3") (pinfunction "3_3") (pintype "unspecified"))
    )
    (net (code "76") (name "TX4") (class "Default")
      (node (ref "U1") (pin "39") (pinfunction "TX4/A3_39") (pintype "unspecified"))
      (node (ref "U43") (pin "10") (pinfunction "10_10") (pintype "unspecified"))
      (node (ref "U6") (pin "4") (pinfunction "4_4") (pintype "unspecified"))
    )
    (net (code "77") (name "TX5") (class "Default")
      (node (ref "CN13") (pin "4") (pinfunction "4_4") (pintype "unspecified"))
      (node (ref "U1") (pin "42") (pinfunction "TX5/A6_42") (pintype "unspecified"))
      (node (ref "U43") (pin "7") (pinfunction "7_7") (pintype "unspecified"))
    )
    (net (code "78") (name "TX7") (class "Default")
      (node (ref "U1") (pin "21") (pinfunction "TX7_21") (pintype "unspecified"))
      (node (ref "U44") (pin "21") (pinfunction "21_21") (pintype "unspecified"))
      (node (ref "U5") (pin "4") (pinfunction "4_4") (pintype "unspecified"))
    )
    (net (code "79") (name "unconnected-(U48-Pad4)") (class "Default")
      (node (ref "U48") (pin "4") (pinfunction "4_4") (pintype "input+no_connect"))
    )
    (net (code "80") (name "unconnected-(U48-Pad5)") (class "Default")
      (node (ref "U48") (pin "5") (pinfunction "5_5") (pintype "input+no_connect"))
    )
  )
)
